# Johnson.net
KiCad netlist of a schematic drawn in EAGLE
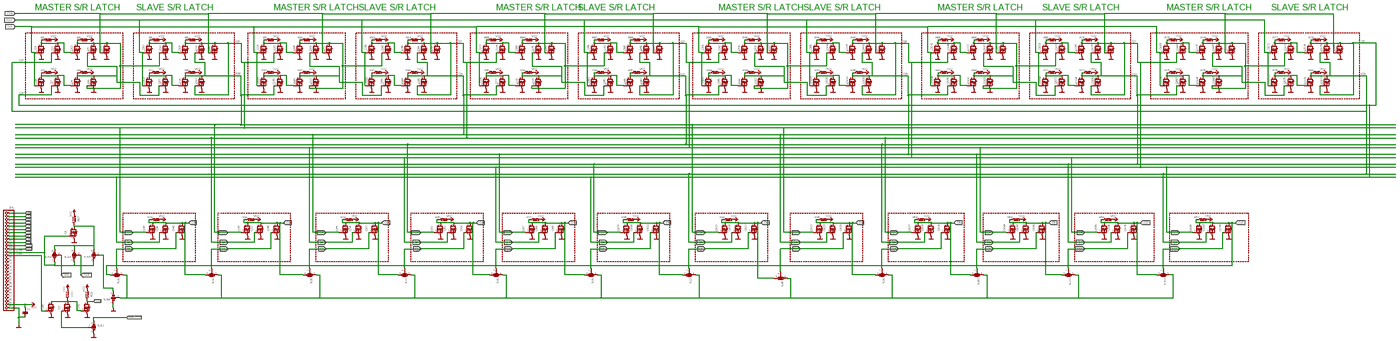
[diagram p0: schematic, sheet 1, overview]
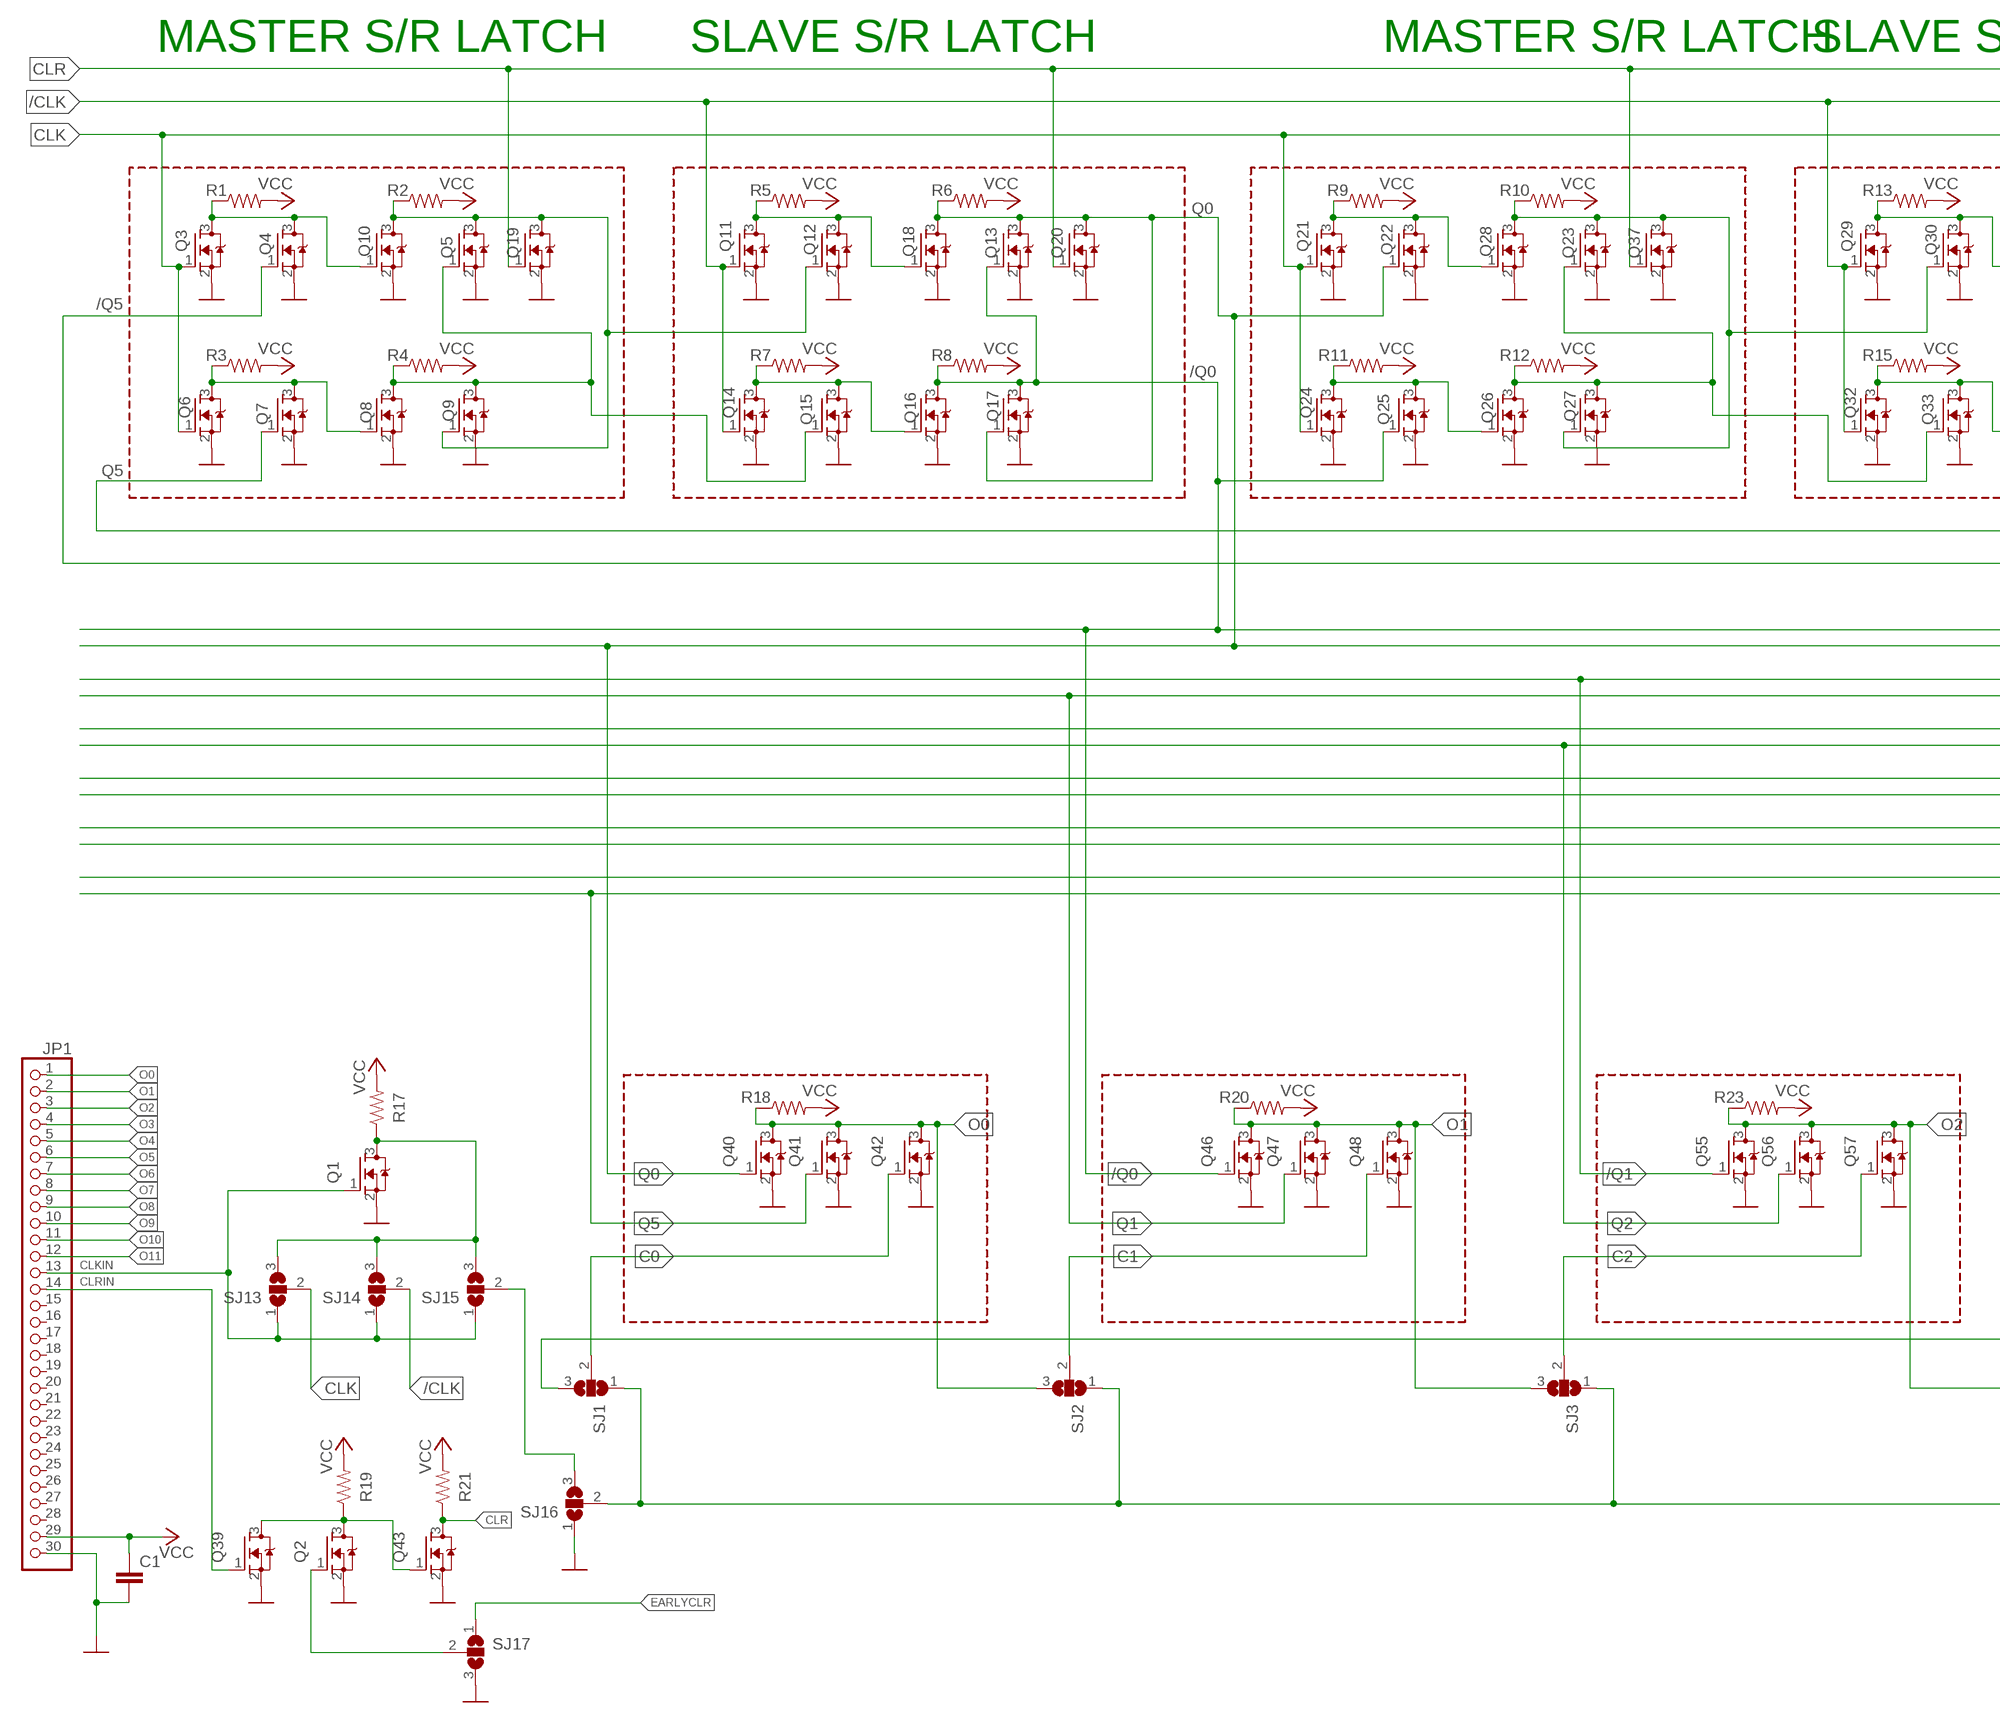
[diagram p1: schematic, sheet 1, part 1 of 4]
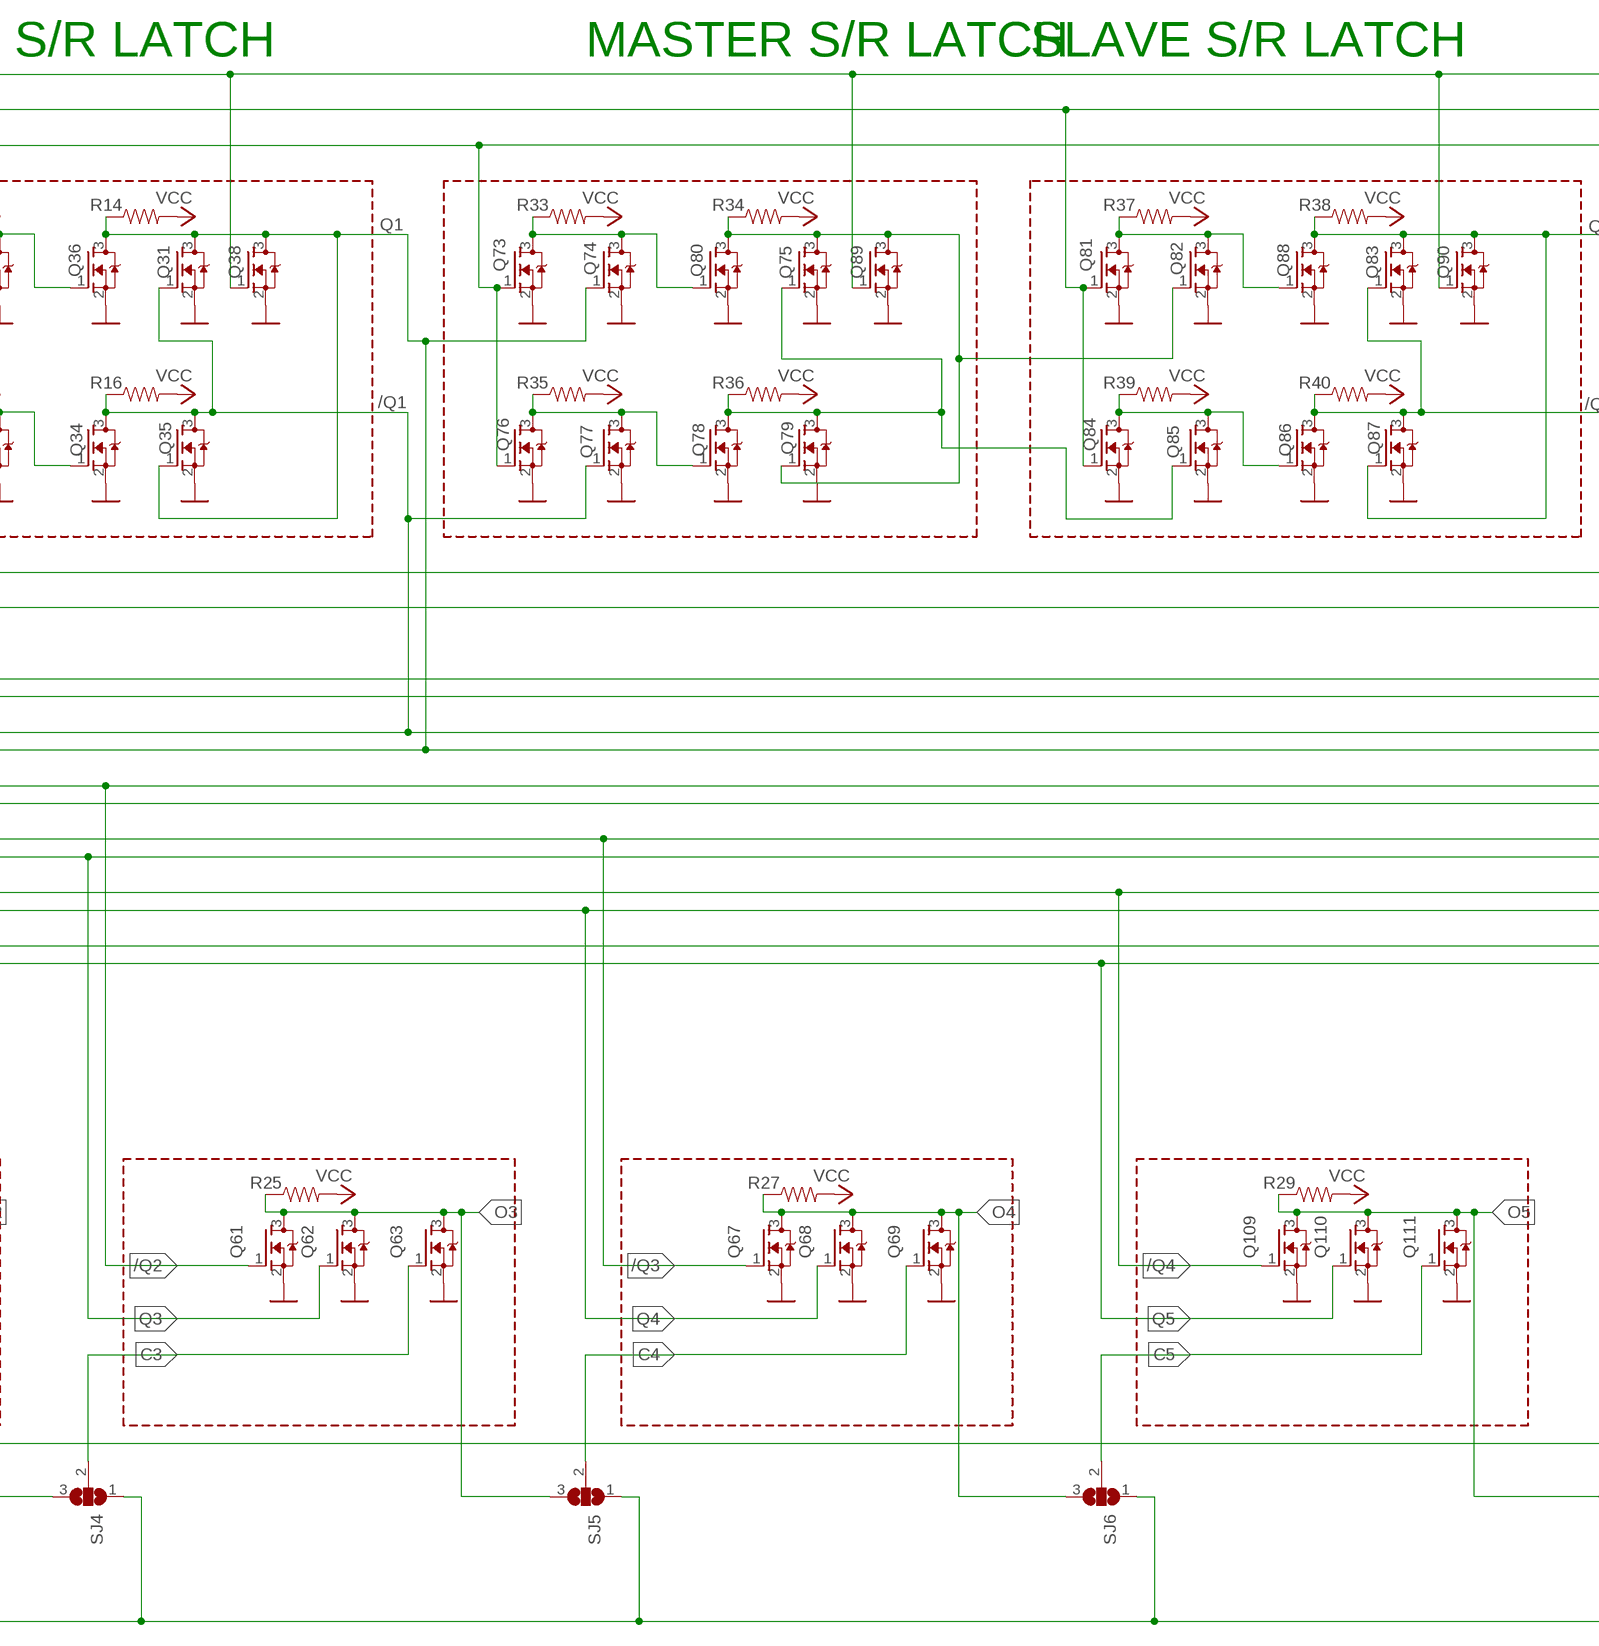
[diagram p2: schematic, sheet 1, part 2 of 4]
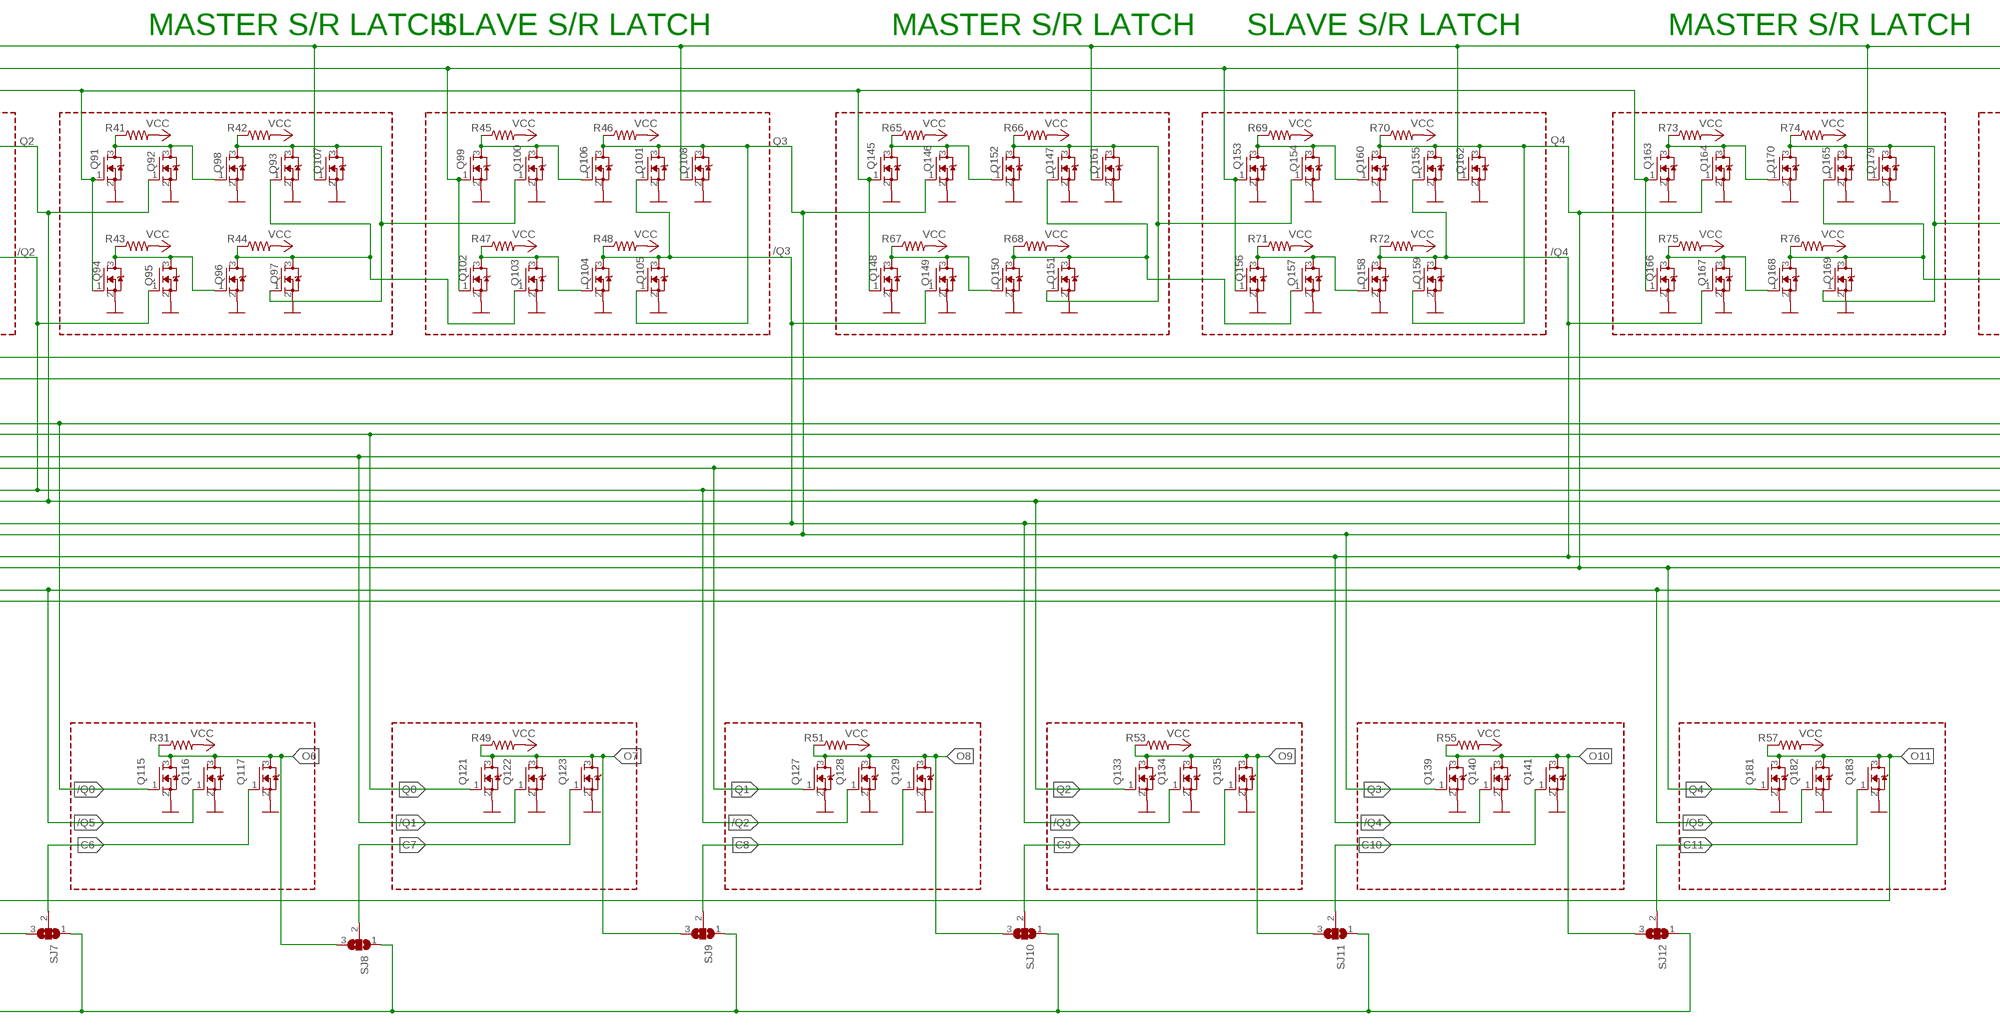
[diagram p3: schematic, sheet 1, part 3 of 4]
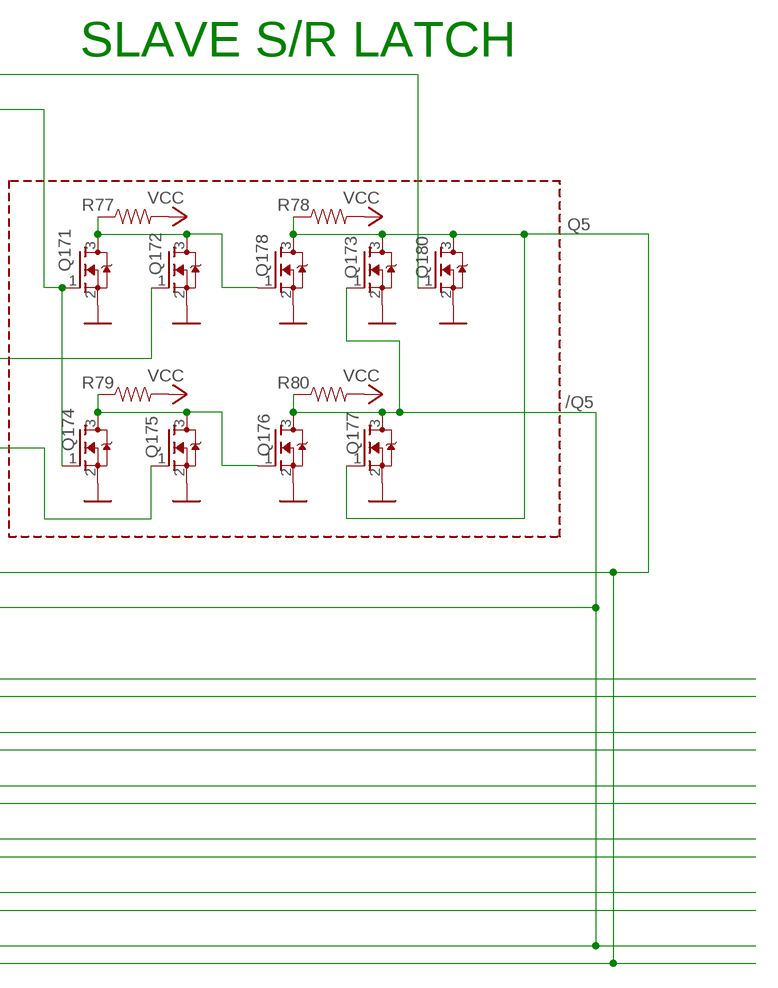
[diagram p4: schematic, sheet 1, part 4 of 4]

(export (version "E")
  (design (tool "Eeschema 10.0.6"))
  (components
    (comp (ref "C1")
      (value "C-EUC0805")
      (footprint "eagle-import:C0805")
      (libsource (lib "eagle-import") (part "C-EUC0805"))
    )
    (comp (ref "JP1")
      (value "PINHD-1X30")
      (footprint "eagle-import:1X30")
      (libsource (lib "eagle-import") (part "PINHD-1X30"))
    )
    (comp (ref "Q1")
      (value "310mA/60V/1.6Ω")
      (footprint "eagle-import:SOT23")
      (libsource (lib "eagle-import") (part "NMOSREFLOW"))
    )
    (comp (ref "Q2")
      (value "310mA/60V/1.6Ω")
      (footprint "eagle-import:SOT23")
      (libsource (lib "eagle-import") (part "NMOSREFLOW"))
    )
    (comp (ref "Q3")
      (value "310mA/60V/1.6Ω")
      (footprint "eagle-import:SOT23")
      (fields (field (name "SPICEPREFIX") "M"))
      (libsource (lib "eagle-import") (part "NMOSREFLOW"))
    )
    (comp (ref "Q4")
      (value "310mA/60V/1.6Ω")
      (footprint "eagle-import:SOT23")
      (libsource (lib "eagle-import") (part "NMOSREFLOW"))
    )
    (comp (ref "Q5")
      (value "310mA/60V/1.6Ω")
      (footprint "eagle-import:SOT23")
      (libsource (lib "eagle-import") (part "NMOSREFLOW"))
    )
    (comp (ref "Q6")
      (value "310mA/60V/1.6Ω")
      (footprint "eagle-import:SOT23")
      (libsource (lib "eagle-import") (part "NMOSREFLOW"))
    )
    (comp (ref "Q7")
      (value "310mA/60V/1.6Ω")
      (footprint "eagle-import:SOT23")
      (libsource (lib "eagle-import") (part "NMOSREFLOW"))
    )
    (comp (ref "Q8")
      (value "310mA/60V/1.6Ω")
      (footprint "eagle-import:SOT23")
      (libsource (lib "eagle-import") (part "NMOSREFLOW"))
    )
    (comp (ref "Q9")
      (value "310mA/60V/1.6Ω")
      (footprint "eagle-import:SOT23")
      (libsource (lib "eagle-import") (part "NMOSREFLOW"))
    )
    (comp (ref "Q10")
      (value "310mA/60V/1.6Ω")
      (footprint "eagle-import:SOT23")
      (fields (field (name "SPICEPREFIX") "M"))
      (libsource (lib "eagle-import") (part "NMOSREFLOW"))
    )
    (comp (ref "Q11")
      (value "310mA/60V/1.6Ω")
      (footprint "eagle-import:SOT23")
      (fields (field (name "SPICEPREFIX") "M"))
      (libsource (lib "eagle-import") (part "NMOSREFLOW"))
    )
    (comp (ref "Q12")
      (value "310mA/60V/1.6Ω")
      (footprint "eagle-import:SOT23")
      (libsource (lib "eagle-import") (part "NMOSREFLOW"))
    )
    (comp (ref "Q13")
      (value "310mA/60V/1.6Ω")
      (footprint "eagle-import:SOT23")
      (libsource (lib "eagle-import") (part "NMOSREFLOW"))
    )
    (comp (ref "Q14")
      (value "310mA/60V/1.6Ω")
      (footprint "eagle-import:SOT23")
      (libsource (lib "eagle-import") (part "NMOSREFLOW"))
    )
    (comp (ref "Q15")
      (value "310mA/60V/1.6Ω")
      (footprint "eagle-import:SOT23")
      (libsource (lib "eagle-import") (part "NMOSREFLOW"))
    )
    (comp (ref "Q16")
      (value "310mA/60V/1.6Ω")
      (footprint "eagle-import:SOT23")
      (libsource (lib "eagle-import") (part "NMOSREFLOW"))
    )
    (comp (ref "Q17")
      (value "310mA/60V/1.6Ω")
      (footprint "eagle-import:SOT23")
      (libsource (lib "eagle-import") (part "NMOSREFLOW"))
    )
    (comp (ref "Q18")
      (value "310mA/60V/1.6Ω")
      (footprint "eagle-import:SOT23")
      (fields (field (name "SPICEPREFIX") "M"))
      (libsource (lib "eagle-import") (part "NMOSREFLOW"))
    )
    (comp (ref "Q19")
      (value "310mA/60V/1.6Ω")
      (footprint "eagle-import:SOT23")
      (libsource (lib "eagle-import") (part "NMOSREFLOW"))
    )
    (comp (ref "Q20")
      (value "310mA/60V/1.6Ω")
      (footprint "eagle-import:SOT23")
      (libsource (lib "eagle-import") (part "NMOSREFLOW"))
    )
    (comp (ref "Q21")
      (value "310mA/60V/1.6Ω")
      (footprint "eagle-import:SOT23")
      (fields (field (name "SPICEPREFIX") "M"))
      (libsource (lib "eagle-import") (part "NMOSREFLOW"))
    )
    (comp (ref "Q22")
      (value "310mA/60V/1.6Ω")
      (footprint "eagle-import:SOT23")
      (libsource (lib "eagle-import") (part "NMOSREFLOW"))
    )
    (comp (ref "Q23")
      (value "310mA/60V/1.6Ω")
      (footprint "eagle-import:SOT23")
      (libsource (lib "eagle-import") (part "NMOSREFLOW"))
    )
    (comp (ref "Q24")
      (value "310mA/60V/1.6Ω")
      (footprint "eagle-import:SOT23")
      (libsource (lib "eagle-import") (part "NMOSREFLOW"))
    )
    (comp (ref "Q25")
      (value "310mA/60V/1.6Ω")
      (footprint "eagle-import:SOT23")
      (libsource (lib "eagle-import") (part "NMOSREFLOW"))
    )
    (comp (ref "Q26")
      (value "310mA/60V/1.6Ω")
      (footprint "eagle-import:SOT23")
      (libsource (lib "eagle-import") (part "NMOSREFLOW"))
    )
    (comp (ref "Q27")
      (value "310mA/60V/1.6Ω")
      (footprint "eagle-import:SOT23")
      (libsource (lib "eagle-import") (part "NMOSREFLOW"))
    )
    (comp (ref "Q28")
      (value "310mA/60V/1.6Ω")
      (footprint "eagle-import:SOT23")
      (fields (field (name "SPICEPREFIX") "M"))
      (libsource (lib "eagle-import") (part "NMOSREFLOW"))
    )
    (comp (ref "Q29")
      (value "310mA/60V/1.6Ω")
      (footprint "eagle-import:SOT23")
      (fields (field (name "SPICEPREFIX") "M"))
      (libsource (lib "eagle-import") (part "NMOSREFLOW"))
    )
    (comp (ref "Q30")
      (value "310mA/60V/1.6Ω")
      (footprint "eagle-import:SOT23")
      (libsource (lib "eagle-import") (part "NMOSREFLOW"))
    )
    (comp (ref "Q31")
      (value "310mA/60V/1.6Ω")
      (footprint "eagle-import:SOT23")
      (libsource (lib "eagle-import") (part "NMOSREFLOW"))
    )
    (comp (ref "Q32")
      (value "310mA/60V/1.6Ω")
      (footprint "eagle-import:SOT23")
      (libsource (lib "eagle-import") (part "NMOSREFLOW"))
    )
    (comp (ref "Q33")
      (value "310mA/60V/1.6Ω")
      (footprint "eagle-import:SOT23")
      (libsource (lib "eagle-import") (part "NMOSREFLOW"))
    )
    (comp (ref "Q34")
      (value "310mA/60V/1.6Ω")
      (footprint "eagle-import:SOT23")
      (libsource (lib "eagle-import") (part "NMOSREFLOW"))
    )
    (comp (ref "Q35")
      (value "310mA/60V/1.6Ω")
      (footprint "eagle-import:SOT23")
      (libsource (lib "eagle-import") (part "NMOSREFLOW"))
    )
    (comp (ref "Q36")
      (value "310mA/60V/1.6Ω")
      (footprint "eagle-import:SOT23")
      (fields (field (name "SPICEPREFIX") "M"))
      (libsource (lib "eagle-import") (part "NMOSREFLOW"))
    )
    (comp (ref "Q37")
      (value "310mA/60V/1.6Ω")
      (footprint "eagle-import:SOT23")
      (libsource (lib "eagle-import") (part "NMOSREFLOW"))
    )
    (comp (ref "Q38")
      (value "310mA/60V/1.6Ω")
      (footprint "eagle-import:SOT23")
      (libsource (lib "eagle-import") (part "NMOSREFLOW"))
    )
    (comp (ref "Q39")
      (value "310mA/60V/1.6Ω")
      (footprint "eagle-import:SOT23")
      (libsource (lib "eagle-import") (part "NMOSREFLOW"))
    )
    (comp (ref "Q40")
      (value "310mA/60V/1.6Ω")
      (footprint "eagle-import:SOT23")
      (libsource (lib "eagle-import") (part "NMOSREFLOW"))
    )
    (comp (ref "Q41")
      (value "310mA/60V/1.6Ω")
      (footprint "eagle-import:SOT23")
      (libsource (lib "eagle-import") (part "NMOSREFLOW"))
    )
    (comp (ref "Q42")
      (value "310mA/60V/1.6Ω")
      (footprint "eagle-import:SOT23")
      (libsource (lib "eagle-import") (part "NMOSREFLOW"))
    )
    (comp (ref "Q43")
      (value "310mA/60V/1.6Ω")
      (footprint "eagle-import:SOT23")
      (libsource (lib "eagle-import") (part "NMOSREFLOW"))
    )
    (comp (ref "Q46")
      (value "310mA/60V/1.6Ω")
      (footprint "eagle-import:SOT23")
      (libsource (lib "eagle-import") (part "NMOSREFLOW"))
    )
    (comp (ref "Q47")
      (value "310mA/60V/1.6Ω")
      (footprint "eagle-import:SOT23")
      (libsource (lib "eagle-import") (part "NMOSREFLOW"))
    )
    (comp (ref "Q48")
      (value "310mA/60V/1.6Ω")
      (footprint "eagle-import:SOT23")
      (libsource (lib "eagle-import") (part "NMOSREFLOW"))
    )
    (comp (ref "Q55")
      (value "310mA/60V/1.6Ω")
      (footprint "eagle-import:SOT23")
      (libsource (lib "eagle-import") (part "NMOSREFLOW"))
    )
    (comp (ref "Q56")
      (value "310mA/60V/1.6Ω")
      (footprint "eagle-import:SOT23")
      (libsource (lib "eagle-import") (part "NMOSREFLOW"))
    )
    (comp (ref "Q57")
      (value "310mA/60V/1.6Ω")
      (footprint "eagle-import:SOT23")
      (libsource (lib "eagle-import") (part "NMOSREFLOW"))
    )
    (comp (ref "Q61")
      (value "310mA/60V/1.6Ω")
      (footprint "eagle-import:SOT23")
      (libsource (lib "eagle-import") (part "NMOSREFLOW"))
    )
    (comp (ref "Q62")
      (value "310mA/60V/1.6Ω")
      (footprint "eagle-import:SOT23")
      (libsource (lib "eagle-import") (part "NMOSREFLOW"))
    )
    (comp (ref "Q63")
      (value "310mA/60V/1.6Ω")
      (footprint "eagle-import:SOT23")
      (libsource (lib "eagle-import") (part "NMOSREFLOW"))
    )
    (comp (ref "Q67")
      (value "310mA/60V/1.6Ω")
      (footprint "eagle-import:SOT23")
      (libsource (lib "eagle-import") (part "NMOSREFLOW"))
    )
    (comp (ref "Q68")
      (value "310mA/60V/1.6Ω")
      (footprint "eagle-import:SOT23")
      (libsource (lib "eagle-import") (part "NMOSREFLOW"))
    )
    (comp (ref "Q69")
      (value "310mA/60V/1.6Ω")
      (footprint "eagle-import:SOT23")
      (libsource (lib "eagle-import") (part "NMOSREFLOW"))
    )
    (comp (ref "Q73")
      (value "310mA/60V/1.6Ω")
      (footprint "eagle-import:SOT23")
      (fields (field (name "SPICEPREFIX") "M"))
      (libsource (lib "eagle-import") (part "NMOSREFLOW"))
    )
    (comp (ref "Q74")
      (value "310mA/60V/1.6Ω")
      (footprint "eagle-import:SOT23")
      (libsource (lib "eagle-import") (part "NMOSREFLOW"))
    )
    (comp (ref "Q75")
      (value "310mA/60V/1.6Ω")
      (footprint "eagle-import:SOT23")
      (libsource (lib "eagle-import") (part "NMOSREFLOW"))
    )
    (comp (ref "Q76")
      (value "310mA/60V/1.6Ω")
      (footprint "eagle-import:SOT23")
      (libsource (lib "eagle-import") (part "NMOSREFLOW"))
    )
    (comp (ref "Q77")
      (value "310mA/60V/1.6Ω")
      (footprint "eagle-import:SOT23")
      (libsource (lib "eagle-import") (part "NMOSREFLOW"))
    )
    (comp (ref "Q78")
      (value "310mA/60V/1.6Ω")
      (footprint "eagle-import:SOT23")
      (libsource (lib "eagle-import") (part "NMOSREFLOW"))
    )
    (comp (ref "Q79")
      (value "310mA/60V/1.6Ω")
      (footprint "eagle-import:SOT23")
      (libsource (lib "eagle-import") (part "NMOSREFLOW"))
    )
    (comp (ref "Q80")
      (value "310mA/60V/1.6Ω")
      (footprint "eagle-import:SOT23")
      (fields (field (name "SPICEPREFIX") "M"))
      (libsource (lib "eagle-import") (part "NMOSREFLOW"))
    )
    (comp (ref "Q81")
      (value "310mA/60V/1.6Ω")
      (footprint "eagle-import:SOT23")
      (fields (field (name "SPICEPREFIX") "M"))
      (libsource (lib "eagle-import") (part "NMOSREFLOW"))
    )
    (comp (ref "Q82")
      (value "310mA/60V/1.6Ω")
      (footprint "eagle-import:SOT23")
      (libsource (lib "eagle-import") (part "NMOSREFLOW"))
    )
    (comp (ref "Q83")
      (value "310mA/60V/1.6Ω")
      (footprint "eagle-import:SOT23")
      (libsource (lib "eagle-import") (part "NMOSREFLOW"))
    )
    (comp (ref "Q84")
      (value "310mA/60V/1.6Ω")
      (footprint "eagle-import:SOT23")
      (libsource (lib "eagle-import") (part "NMOSREFLOW"))
    )
    (comp (ref "Q85")
      (value "310mA/60V/1.6Ω")
      (footprint "eagle-import:SOT23")
      (libsource (lib "eagle-import") (part "NMOSREFLOW"))
    )
    (comp (ref "Q86")
      (value "310mA/60V/1.6Ω")
      (footprint "eagle-import:SOT23")
      (libsource (lib "eagle-import") (part "NMOSREFLOW"))
    )
    (comp (ref "Q87")
      (value "310mA/60V/1.6Ω")
      (footprint "eagle-import:SOT23")
      (libsource (lib "eagle-import") (part "NMOSREFLOW"))
    )
    (comp (ref "Q88")
      (value "310mA/60V/1.6Ω")
      (footprint "eagle-import:SOT23")
      (fields (field (name "SPICEPREFIX") "M"))
      (libsource (lib "eagle-import") (part "NMOSREFLOW"))
    )
    (comp (ref "Q89")
      (value "310mA/60V/1.6Ω")
      (footprint "eagle-import:SOT23")
      (libsource (lib "eagle-import") (part "NMOSREFLOW"))
    )
    (comp (ref "Q90")
      (value "310mA/60V/1.6Ω")
      (footprint "eagle-import:SOT23")
      (libsource (lib "eagle-import") (part "NMOSREFLOW"))
    )
    (comp (ref "Q91")
      (value "310mA/60V/1.6Ω")
      (footprint "eagle-import:SOT23")
      (fields (field (name "SPICEPREFIX") "M"))
      (libsource (lib "eagle-import") (part "NMOSREFLOW"))
    )
    (comp (ref "Q92")
      (value "310mA/60V/1.6Ω")
      (footprint "eagle-import:SOT23")
      (libsource (lib "eagle-import") (part "NMOSREFLOW"))
    )
    (comp (ref "Q93")
      (value "310mA/60V/1.6Ω")
      (footprint "eagle-import:SOT23")
      (libsource (lib "eagle-import") (part "NMOSREFLOW"))
    )
    (comp (ref "Q94")
      (value "310mA/60V/1.6Ω")
      (footprint "eagle-import:SOT23")
      (libsource (lib "eagle-import") (part "NMOSREFLOW"))
    )
    (comp (ref "Q95")
      (value "310mA/60V/1.6Ω")
      (footprint "eagle-import:SOT23")
      (libsource (lib "eagle-import") (part "NMOSREFLOW"))
    )
    (comp (ref "Q96")
      (value "310mA/60V/1.6Ω")
      (footprint "eagle-import:SOT23")
      (libsource (lib "eagle-import") (part "NMOSREFLOW"))
    )
    (comp (ref "Q97")
      (value "310mA/60V/1.6Ω")
      (footprint "eagle-import:SOT23")
      (libsource (lib "eagle-import") (part "NMOSREFLOW"))
    )
    (comp (ref "Q98")
      (value "310mA/60V/1.6Ω")
      (footprint "eagle-import:SOT23")
      (fields (field (name "SPICEPREFIX") "M"))
      (libsource (lib "eagle-import") (part "NMOSREFLOW"))
    )
    (comp (ref "Q99")
      (value "310mA/60V/1.6Ω")
      (footprint "eagle-import:SOT23")
      (fields (field (name "SPICEPREFIX") "M"))
      (libsource (lib "eagle-import") (part "NMOSREFLOW"))
    )
    (comp (ref "Q100")
      (value "310mA/60V/1.6Ω")
      (footprint "eagle-import:SOT23")
      (libsource (lib "eagle-import") (part "NMOSREFLOW"))
    )
    (comp (ref "Q101")
      (value "310mA/60V/1.6Ω")
      (footprint "eagle-import:SOT23")
      (libsource (lib "eagle-import") (part "NMOSREFLOW"))
    )
    (comp (ref "Q102")
      (value "310mA/60V/1.6Ω")
      (footprint "eagle-import:SOT23")
      (libsource (lib "eagle-import") (part "NMOSREFLOW"))
    )
    (comp (ref "Q103")
      (value "310mA/60V/1.6Ω")
      (footprint "eagle-import:SOT23")
      (libsource (lib "eagle-import") (part "NMOSREFLOW"))
    )
    (comp (ref "Q104")
      (value "310mA/60V/1.6Ω")
      (footprint "eagle-import:SOT23")
      (libsource (lib "eagle-import") (part "NMOSREFLOW"))
    )
    (comp (ref "Q105")
      (value "310mA/60V/1.6Ω")
      (footprint "eagle-import:SOT23")
      (libsource (lib "eagle-import") (part "NMOSREFLOW"))
    )
    (comp (ref "Q106")
      (value "310mA/60V/1.6Ω")
      (footprint "eagle-import:SOT23")
      (fields (field (name "SPICEPREFIX") "M"))
      (libsource (lib "eagle-import") (part "NMOSREFLOW"))
    )
    (comp (ref "Q107")
      (value "310mA/60V/1.6Ω")
      (footprint "eagle-import:SOT23")
      (libsource (lib "eagle-import") (part "NMOSREFLOW"))
    )
    (comp (ref "Q108")
      (value "310mA/60V/1.6Ω")
      (footprint "eagle-import:SOT23")
      (libsource (lib "eagle-import") (part "NMOSREFLOW"))
    )
    (comp (ref "Q109")
      (value "310mA/60V/1.6Ω")
      (footprint "eagle-import:SOT23")
      (libsource (lib "eagle-import") (part "NMOSREFLOW"))
    )
    (comp (ref "Q110")
      (value "310mA/60V/1.6Ω")
      (footprint "eagle-import:SOT23")
      (libsource (lib "eagle-import") (part "NMOSREFLOW"))
    )
    (comp (ref "Q111")
      (value "310mA/60V/1.6Ω")
      (footprint "eagle-import:SOT23")
      (libsource (lib "eagle-import") (part "NMOSREFLOW"))
    )
    (comp (ref "Q115")
      (value "310mA/60V/1.6Ω")
      (footprint "eagle-import:SOT23")
      (libsource (lib "eagle-import") (part "NMOSREFLOW"))
    )
    (comp (ref "Q116")
      (value "310mA/60V/1.6Ω")
      (footprint "eagle-import:SOT23")
      (libsource (lib "eagle-import") (part "NMOSREFLOW"))
    )
    (comp (ref "Q117")
      (value "310mA/60V/1.6Ω")
      (footprint "eagle-import:SOT23")
      (libsource (lib "eagle-import") (part "NMOSREFLOW"))
    )
    (comp (ref "Q121")
      (value "310mA/60V/1.6Ω")
      (footprint "eagle-import:SOT23")
      (libsource (lib "eagle-import") (part "NMOSREFLOW"))
    )
    (comp (ref "Q122")
      (value "310mA/60V/1.6Ω")
      (footprint "eagle-import:SOT23")
      (libsource (lib "eagle-import") (part "NMOSREFLOW"))
    )
    (comp (ref "Q123")
      (value "310mA/60V/1.6Ω")
      (footprint "eagle-import:SOT23")
      (libsource (lib "eagle-import") (part "NMOSREFLOW"))
    )
    (comp (ref "Q127")
      (value "310mA/60V/1.6Ω")
      (footprint "eagle-import:SOT23")
      (libsource (lib "eagle-import") (part "NMOSREFLOW"))
    )
    (comp (ref "Q128")
      (value "310mA/60V/1.6Ω")
      (footprint "eagle-import:SOT23")
      (libsource (lib "eagle-import") (part "NMOSREFLOW"))
    )
    (comp (ref "Q129")
      (value "310mA/60V/1.6Ω")
      (footprint "eagle-import:SOT23")
      (libsource (lib "eagle-import") (part "NMOSREFLOW"))
    )
    (comp (ref "Q133")
      (value "310mA/60V/1.6Ω")
      (footprint "eagle-import:SOT23")
      (libsource (lib "eagle-import") (part "NMOSREFLOW"))
    )
    (comp (ref "Q134")
      (value "310mA/60V/1.6Ω")
      (footprint "eagle-import:SOT23")
      (libsource (lib "eagle-import") (part "NMOSREFLOW"))
    )
    (comp (ref "Q135")
      (value "310mA/60V/1.6Ω")
      (footprint "eagle-import:SOT23")
      (libsource (lib "eagle-import") (part "NMOSREFLOW"))
    )
    (comp (ref "Q139")
      (value "310mA/60V/1.6Ω")
      (footprint "eagle-import:SOT23")
      (libsource (lib "eagle-import") (part "NMOSREFLOW"))
    )
    (comp (ref "Q140")
      (value "310mA/60V/1.6Ω")
      (footprint "eagle-import:SOT23")
      (libsource (lib "eagle-import") (part "NMOSREFLOW"))
    )
    (comp (ref "Q141")
      (value "310mA/60V/1.6Ω")
      (footprint "eagle-import:SOT23")
      (libsource (lib "eagle-import") (part "NMOSREFLOW"))
    )
    (comp (ref "Q145")
      (value "310mA/60V/1.6Ω")
      (footprint "eagle-import:SOT23")
      (fields (field (name "SPICEPREFIX") "M"))
      (libsource (lib "eagle-import") (part "NMOSREFLOW"))
    )
    (comp (ref "Q146")
      (value "310mA/60V/1.6Ω")
      (footprint "eagle-import:SOT23")
      (libsource (lib "eagle-import") (part "NMOSREFLOW"))
    )
    (comp (ref "Q147")
      (value "310mA/60V/1.6Ω")
      (footprint "eagle-import:SOT23")
      (libsource (lib "eagle-import") (part "NMOSREFLOW"))
    )
    (comp (ref "Q148")
      (value "310mA/60V/1.6Ω")
      (footprint "eagle-import:SOT23")
      (libsource (lib "eagle-import") (part "NMOSREFLOW"))
    )
    (comp (ref "Q149")
      (value "310mA/60V/1.6Ω")
      (footprint "eagle-import:SOT23")
      (libsource (lib "eagle-import") (part "NMOSREFLOW"))
    )
    (comp (ref "Q150")
      (value "310mA/60V/1.6Ω")
      (footprint "eagle-import:SOT23")
      (libsource (lib "eagle-import") (part "NMOSREFLOW"))
    )
    (comp (ref "Q151")
      (value "310mA/60V/1.6Ω")
      (footprint "eagle-import:SOT23")
      (libsource (lib "eagle-import") (part "NMOSREFLOW"))
    )
    (comp (ref "Q152")
      (value "310mA/60V/1.6Ω")
      (footprint "eagle-import:SOT23")
      (fields (field (name "SPICEPREFIX") "M"))
      (libsource (lib "eagle-import") (part "NMOSREFLOW"))
    )
    (comp (ref "Q153")
      (value "310mA/60V/1.6Ω")
      (footprint "eagle-import:SOT23")
      (fields (field (name "SPICEPREFIX") "M"))
      (libsource (lib "eagle-import") (part "NMOSREFLOW"))
    )
    (comp (ref "Q154")
      (value "310mA/60V/1.6Ω")
      (footprint "eagle-import:SOT23")
      (libsource (lib "eagle-import") (part "NMOSREFLOW"))
    )
    (comp (ref "Q155")
      (value "310mA/60V/1.6Ω")
      (footprint "eagle-import:SOT23")
      (libsource (lib "eagle-import") (part "NMOSREFLOW"))
    )
    (comp (ref "Q156")
      (value "310mA/60V/1.6Ω")
      (footprint "eagle-import:SOT23")
      (libsource (lib "eagle-import") (part "NMOSREFLOW"))
    )
    (comp (ref "Q157")
      (value "310mA/60V/1.6Ω")
      (footprint "eagle-import:SOT23")
      (libsource (lib "eagle-import") (part "NMOSREFLOW"))
    )
    (comp (ref "Q158")
      (value "310mA/60V/1.6Ω")
      (footprint "eagle-import:SOT23")
      (libsource (lib "eagle-import") (part "NMOSREFLOW"))
    )
    (comp (ref "Q159")
      (value "310mA/60V/1.6Ω")
      (footprint "eagle-import:SOT23")
      (libsource (lib "eagle-import") (part "NMOSREFLOW"))
    )
    (comp (ref "Q160")
      (value "310mA/60V/1.6Ω")
      (footprint "eagle-import:SOT23")
      (fields (field (name "SPICEPREFIX") "M"))
      (libsource (lib "eagle-import") (part "NMOSREFLOW"))
    )
    (comp (ref "Q161")
      (value "310mA/60V/1.6Ω")
      (footprint "eagle-import:SOT23")
      (libsource (lib "eagle-import") (part "NMOSREFLOW"))
    )
    (comp (ref "Q162")
      (value "310mA/60V/1.6Ω")
      (footprint "eagle-import:SOT23")
      (libsource (lib "eagle-import") (part "NMOSREFLOW"))
    )
    (comp (ref "Q163")
      (value "310mA/60V/1.6Ω")
      (footprint "eagle-import:SOT23")
      (fields (field (name "SPICEPREFIX") "M"))
      (libsource (lib "eagle-import") (part "NMOSREFLOW"))
    )
    (comp (ref "Q164")
      (value "310mA/60V/1.6Ω")
      (footprint "eagle-import:SOT23")
      (libsource (lib "eagle-import") (part "NMOSREFLOW"))
    )
    (comp (ref "Q165")
      (value "310mA/60V/1.6Ω")
      (footprint "eagle-import:SOT23")
      (libsource (lib "eagle-import") (part "NMOSREFLOW"))
    )
    (comp (ref "Q166")
      (value "310mA/60V/1.6Ω")
      (footprint "eagle-import:SOT23")
      (libsource (lib "eagle-import") (part "NMOSREFLOW"))
    )
    (comp (ref "Q167")
      (value "310mA/60V/1.6Ω")
      (footprint "eagle-import:SOT23")
      (libsource (lib "eagle-import") (part "NMOSREFLOW"))
    )
    (comp (ref "Q168")
      (value "310mA/60V/1.6Ω")
      (footprint "eagle-import:SOT23")
      (libsource (lib "eagle-import") (part "NMOSREFLOW"))
    )
    (comp (ref "Q169")
      (value "310mA/60V/1.6Ω")
      (footprint "eagle-import:SOT23")
      (libsource (lib "eagle-import") (part "NMOSREFLOW"))
    )
    (comp (ref "Q170")
      (value "310mA/60V/1.6Ω")
      (footprint "eagle-import:SOT23")
      (fields (field (name "SPICEPREFIX") "M"))
      (libsource (lib "eagle-import") (part "NMOSREFLOW"))
    )
    (comp (ref "Q171")
      (value "310mA/60V/1.6Ω")
      (footprint "eagle-import:SOT23")
      (fields (field (name "SPICEPREFIX") "M"))
      (libsource (lib "eagle-import") (part "NMOSREFLOW"))
    )
    (comp (ref "Q172")
      (value "310mA/60V/1.6Ω")
      (footprint "eagle-import:SOT23")
      (libsource (lib "eagle-import") (part "NMOSREFLOW"))
    )
    (comp (ref "Q173")
      (value "310mA/60V/1.6Ω")
      (footprint "eagle-import:SOT23")
      (libsource (lib "eagle-import") (part "NMOSREFLOW"))
    )
    (comp (ref "Q174")
      (value "310mA/60V/1.6Ω")
      (footprint "eagle-import:SOT23")
      (libsource (lib "eagle-import") (part "NMOSREFLOW"))
    )
    (comp (ref "Q175")
      (value "310mA/60V/1.6Ω")
      (footprint "eagle-import:SOT23")
      (libsource (lib "eagle-import") (part "NMOSREFLOW"))
    )
    (comp (ref "Q176")
      (value "310mA/60V/1.6Ω")
      (footprint "eagle-import:SOT23")
      (libsource (lib "eagle-import") (part "NMOSREFLOW"))
    )
    (comp (ref "Q177")
      (value "310mA/60V/1.6Ω")
      (footprint "eagle-import:SOT23")
      (libsource (lib "eagle-import") (part "NMOSREFLOW"))
    )
    (comp (ref "Q178")
      (value "310mA/60V/1.6Ω")
      (footprint "eagle-import:SOT23")
      (fields (field (name "SPICEPREFIX") "M"))
      (libsource (lib "eagle-import") (part "NMOSREFLOW"))
    )
    (comp (ref "Q179")
      (value "310mA/60V/1.6Ω")
      (footprint "eagle-import:SOT23")
      (libsource (lib "eagle-import") (part "NMOSREFLOW"))
    )
    (comp (ref "Q180")
      (value "310mA/60V/1.6Ω")
      (footprint "eagle-import:SOT23")
      (libsource (lib "eagle-import") (part "NMOSREFLOW"))
    )
    (comp (ref "Q181")
      (value "310mA/60V/1.6Ω")
      (footprint "eagle-import:SOT23")
      (libsource (lib "eagle-import") (part "NMOSREFLOW"))
    )
    (comp (ref "Q182")
      (value "310mA/60V/1.6Ω")
      (footprint "eagle-import:SOT23")
      (libsource (lib "eagle-import") (part "NMOSREFLOW"))
    )
    (comp (ref "Q183")
      (value "310mA/60V/1.6Ω")
      (footprint "eagle-import:SOT23")
      (libsource (lib "eagle-import") (part "NMOSREFLOW"))
    )
    (comp (ref "R1")
      (value "RESISTOR0805")
      (footprint "eagle-import:0805")
      (libsource (lib "eagle-import") (part "RESISTOR0805"))
    )
    (comp (ref "R2")
      (value "RESISTOR0805")
      (footprint "eagle-import:0805")
      (libsource (lib "eagle-import") (part "RESISTOR0805"))
    )
    (comp (ref "R3")
      (value "RESISTOR0805")
      (footprint "eagle-import:0805")
      (libsource (lib "eagle-import") (part "RESISTOR0805"))
    )
    (comp (ref "R4")
      (value "RESISTOR0805")
      (footprint "eagle-import:0805")
      (libsource (lib "eagle-import") (part "RESISTOR0805"))
    )
    (comp (ref "R5")
      (value "RESISTOR0805")
      (footprint "eagle-import:0805")
      (libsource (lib "eagle-import") (part "RESISTOR0805"))
    )
    (comp (ref "R6")
      (value "RESISTOR0805")
      (footprint "eagle-import:0805")
      (libsource (lib "eagle-import") (part "RESISTOR0805"))
    )
    (comp (ref "R7")
      (value "RESISTOR0805")
      (footprint "eagle-import:0805")
      (libsource (lib "eagle-import") (part "RESISTOR0805"))
    )
    (comp (ref "R8")
      (value "RESISTOR0805")
      (footprint "eagle-import:0805")
      (libsource (lib "eagle-import") (part "RESISTOR0805"))
    )
    (comp (ref "R9")
      (value "RESISTOR0805")
      (footprint "eagle-import:0805")
      (libsource (lib "eagle-import") (part "RESISTOR0805"))
    )
    (comp (ref "R10")
      (value "RESISTOR0805")
      (footprint "eagle-import:0805")
      (libsource (lib "eagle-import") (part "RESISTOR0805"))
    )
    (comp (ref "R11")
      (value "RESISTOR0805")
      (footprint "eagle-import:0805")
      (libsource (lib "eagle-import") (part "RESISTOR0805"))
    )
    (comp (ref "R12")
      (value "RESISTOR0805")
      (footprint "eagle-import:0805")
      (libsource (lib "eagle-import") (part "RESISTOR0805"))
    )
    (comp (ref "R13")
      (value "RESISTOR0805")
      (footprint "eagle-import:0805")
      (libsource (lib "eagle-import") (part "RESISTOR0805"))
    )
    (comp (ref "R14")
      (value "RESISTOR0805")
      (footprint "eagle-import:0805")
      (libsource (lib "eagle-import") (part "RESISTOR0805"))
    )
    (comp (ref "R15")
      (value "RESISTOR0805")
      (footprint "eagle-import:0805")
      (libsource (lib "eagle-import") (part "RESISTOR0805"))
    )
    (comp (ref "R16")
      (value "RESISTOR0805")
      (footprint "eagle-import:0805")
      (libsource (lib "eagle-import") (part "RESISTOR0805"))
    )
    (comp (ref "R17")
      (value "RESISTOR0805")
      (footprint "eagle-import:0805")
      (libsource (lib "eagle-import") (part "RESISTOR0805"))
    )
    (comp (ref "R18")
      (value "RESISTOR0805")
      (footprint "eagle-import:0805")
      (libsource (lib "eagle-import") (part "RESISTOR0805"))
    )
    (comp (ref "R19")
      (value "RESISTOR0805")
      (footprint "eagle-import:0805")
      (libsource (lib "eagle-import") (part "RESISTOR0805"))
    )
    (comp (ref "R20")
      (value "RESISTOR0805")
      (footprint "eagle-import:0805")
      (libsource (lib "eagle-import") (part "RESISTOR0805"))
    )
    (comp (ref "R21")
      (value "RESISTOR0805")
      (footprint "eagle-import:0805")
      (libsource (lib "eagle-import") (part "RESISTOR0805"))
    )
    (comp (ref "R23")
      (value "RESISTOR0805")
      (footprint "eagle-import:0805")
      (libsource (lib "eagle-import") (part "RESISTOR0805"))
    )
    (comp (ref "R25")
      (value "RESISTOR0805")
      (footprint "eagle-import:0805")
      (libsource (lib "eagle-import") (part "RESISTOR0805"))
    )
    (comp (ref "R27")
      (value "RESISTOR0805")
      (footprint "eagle-import:0805")
      (libsource (lib "eagle-import") (part "RESISTOR0805"))
    )
    (comp (ref "R29")
      (value "RESISTOR0805")
      (footprint "eagle-import:0805")
      (libsource (lib "eagle-import") (part "RESISTOR0805"))
    )
    (comp (ref "R31")
      (value "RESISTOR0805")
      (footprint "eagle-import:0805")
      (libsource (lib "eagle-import") (part "RESISTOR0805"))
    )
    (comp (ref "R33")
      (value "RESISTOR0805")
      (footprint "eagle-import:0805")
      (libsource (lib "eagle-import") (part "RESISTOR0805"))
    )
    (comp (ref "R34")
      (value "RESISTOR0805")
      (footprint "eagle-import:0805")
      (libsource (lib "eagle-import") (part "RESISTOR0805"))
    )
    (comp (ref "R35")
      (value "RESISTOR0805")
      (footprint "eagle-import:0805")
      (libsource (lib "eagle-import") (part "RESISTOR0805"))
    )
    (comp (ref "R36")
      (value "RESISTOR0805")
      (footprint "eagle-import:0805")
      (libsource (lib "eagle-import") (part "RESISTOR0805"))
    )
    (comp (ref "R37")
      (value "RESISTOR0805")
      (footprint "eagle-import:0805")
      (libsource (lib "eagle-import") (part "RESISTOR0805"))
    )
    (comp (ref "R38")
      (value "RESISTOR0805")
      (footprint "eagle-import:0805")
      (libsource (lib "eagle-import") (part "RESISTOR0805"))
    )
    (comp (ref "R39")
      (value "RESISTOR0805")
      (footprint "eagle-import:0805")
      (libsource (lib "eagle-import") (part "RESISTOR0805"))
    )
    (comp (ref "R40")
      (value "RESISTOR0805")
      (footprint "eagle-import:0805")
      (libsource (lib "eagle-import") (part "RESISTOR0805"))
    )
    (comp (ref "R41")
      (value "RESISTOR0805")
      (footprint "eagle-import:0805")
      (libsource (lib "eagle-import") (part "RESISTOR0805"))
    )
    (comp (ref "R42")
      (value "RESISTOR0805")
      (footprint "eagle-import:0805")
      (libsource (lib "eagle-import") (part "RESISTOR0805"))
    )
    (comp (ref "R43")
      (value "RESISTOR0805")
      (footprint "eagle-import:0805")
      (libsource (lib "eagle-import") (part "RESISTOR0805"))
    )
    (comp (ref "R44")
      (value "RESISTOR0805")
      (footprint "eagle-import:0805")
      (libsource (lib "eagle-import") (part "RESISTOR0805"))
    )
    (comp (ref "R45")
      (value "RESISTOR0805")
      (footprint "eagle-import:0805")
      (libsource (lib "eagle-import") (part "RESISTOR0805"))
    )
    (comp (ref "R46")
      (value "RESISTOR0805")
      (footprint "eagle-import:0805")
      (libsource (lib "eagle-import") (part "RESISTOR0805"))
    )
    (comp (ref "R47")
      (value "RESISTOR0805")
      (footprint "eagle-import:0805")
      (libsource (lib "eagle-import") (part "RESISTOR0805"))
    )
    (comp (ref "R48")
      (value "RESISTOR0805")
      (footprint "eagle-import:0805")
      (libsource (lib "eagle-import") (part "RESISTOR0805"))
    )
    (comp (ref "R49")
      (value "RESISTOR0805")
      (footprint "eagle-import:0805")
      (libsource (lib "eagle-import") (part "RESISTOR0805"))
    )
    (comp (ref "R51")
      (value "RESISTOR0805")
      (footprint "eagle-import:0805")
      (libsource (lib "eagle-import") (part "RESISTOR0805"))
    )
    (comp (ref "R53")
      (value "RESISTOR0805")
      (footprint "eagle-import:0805")
      (libsource (lib "eagle-import") (part "RESISTOR0805"))
    )
    (comp (ref "R55")
      (value "RESISTOR0805")
      (footprint "eagle-import:0805")
      (libsource (lib "eagle-import") (part "RESISTOR0805"))
    )
    (comp (ref "R57")
      (value "RESISTOR0805")
      (footprint "eagle-import:0805")
      (libsource (lib "eagle-import") (part "RESISTOR0805"))
    )
    (comp (ref "R65")
      (value "RESISTOR0805")
      (footprint "eagle-import:0805")
      (libsource (lib "eagle-import") (part "RESISTOR0805"))
    )
    (comp (ref "R66")
      (value "RESISTOR0805")
      (footprint "eagle-import:0805")
      (libsource (lib "eagle-import") (part "RESISTOR0805"))
    )
    (comp (ref "R67")
      (value "RESISTOR0805")
      (footprint "eagle-import:0805")
      (libsource (lib "eagle-import") (part "RESISTOR0805"))
    )
    (comp (ref "R68")
      (value "RESISTOR0805")
      (footprint "eagle-import:0805")
      (libsource (lib "eagle-import") (part "RESISTOR0805"))
    )
    (comp (ref "R69")
      (value "RESISTOR0805")
      (footprint "eagle-import:0805")
      (libsource (lib "eagle-import") (part "RESISTOR0805"))
    )
    (comp (ref "R70")
      (value "RESISTOR0805")
      (footprint "eagle-import:0805")
      (libsource (lib "eagle-import") (part "RESISTOR0805"))
    )
    (comp (ref "R71")
      (value "RESISTOR0805")
      (footprint "eagle-import:0805")
      (libsource (lib "eagle-import") (part "RESISTOR0805"))
    )
    (comp (ref "R72")
      (value "RESISTOR0805")
      (footprint "eagle-import:0805")
      (libsource (lib "eagle-import") (part "RESISTOR0805"))
    )
    (comp (ref "R73")
      (value "RESISTOR0805")
      (footprint "eagle-import:0805")
      (libsource (lib "eagle-import") (part "RESISTOR0805"))
    )
    (comp (ref "R74")
      (value "RESISTOR0805")
      (footprint "eagle-import:0805")
      (libsource (lib "eagle-import") (part "RESISTOR0805"))
    )
    (comp (ref "R75")
      (value "RESISTOR0805")
      (footprint "eagle-import:0805")
      (libsource (lib "eagle-import") (part "RESISTOR0805"))
    )
    (comp (ref "R76")
      (value "RESISTOR0805")
      (footprint "eagle-import:0805")
      (libsource (lib "eagle-import") (part "RESISTOR0805"))
    )
    (comp (ref "R77")
      (value "RESISTOR0805")
      (footprint "eagle-import:0805")
      (libsource (lib "eagle-import") (part "RESISTOR0805"))
    )
    (comp (ref "R78")
      (value "RESISTOR0805")
      (footprint "eagle-import:0805")
      (libsource (lib "eagle-import") (part "RESISTOR0805"))
    )
    (comp (ref "R79")
      (value "RESISTOR0805")
      (footprint "eagle-import:0805")
      (libsource (lib "eagle-import") (part "RESISTOR0805"))
    )
    (comp (ref "R80")
      (value "RESISTOR0805")
      (footprint "eagle-import:0805")
      (libsource (lib "eagle-import") (part "RESISTOR0805"))
    )
    (comp (ref "SJ1")
      (value "SJ2W")
      (footprint "eagle-import:SJ_2")
      (libsource (lib "eagle-import") (part "SJ2W"))
    )
    (comp (ref "SJ2")
      (value "SJ2W")
      (footprint "eagle-import:SJ_2")
      (libsource (lib "eagle-import") (part "SJ2W"))
    )
    (comp (ref "SJ3")
      (value "SJ2W")
      (footprint "eagle-import:SJ_2")
      (libsource (lib "eagle-import") (part "SJ2W"))
    )
    (comp (ref "SJ4")
      (value "SJ2W")
      (footprint "eagle-import:SJ_2")
      (libsource (lib "eagle-import") (part "SJ2W"))
    )
    (comp (ref "SJ5")
      (value "SJ2W")
      (footprint "eagle-import:SJ_2")
      (libsource (lib "eagle-import") (part "SJ2W"))
    )
    (comp (ref "SJ6")
      (value "SJ2W")
      (footprint "eagle-import:SJ_2")
      (libsource (lib "eagle-import") (part "SJ2W"))
    )
    (comp (ref "SJ7")
      (value "SJ2W")
      (footprint "eagle-import:SJ_2")
      (libsource (lib "eagle-import") (part "SJ2W"))
    )
    (comp (ref "SJ8")
      (value "SJ2W")
      (footprint "eagle-import:SJ_2")
      (libsource (lib "eagle-import") (part "SJ2W"))
    )
    (comp (ref "SJ9")
      (value "SJ2W")
      (footprint "eagle-import:SJ_2")
      (libsource (lib "eagle-import") (part "SJ2W"))
    )
    (comp (ref "SJ10")
      (value "SJ2W")
      (footprint "eagle-import:SJ_2")
      (libsource (lib "eagle-import") (part "SJ2W"))
    )
    (comp (ref "SJ11")
      (value "SJ2W")
      (footprint "eagle-import:SJ_2")
      (libsource (lib "eagle-import") (part "SJ2W"))
    )
    (comp (ref "SJ12")
      (value "SJ2W")
      (footprint "eagle-import:SJ_2")
      (libsource (lib "eagle-import") (part "SJ2W"))
    )
    (comp (ref "SJ13")
      (value "SJ2W")
      (footprint "eagle-import:SJ_2")
      (libsource (lib "eagle-import") (part "SJ2W"))
    )
    (comp (ref "SJ14")
      (value "SJ2W")
      (footprint "eagle-import:SJ_2")
      (libsource (lib "eagle-import") (part "SJ2W"))
    )
    (comp (ref "SJ15")
      (value "SJ2W")
      (footprint "eagle-import:SJ_2")
      (libsource (lib "eagle-import") (part "SJ2W"))
    )
    (comp (ref "SJ16")
      (value "SJ2W")
      (footprint "eagle-import:SJ_2")
      (libsource (lib "eagle-import") (part "SJ2W"))
    )
    (comp (ref "SJ17")
      (value "SJ2W")
      (footprint "eagle-import:SJ_2")
      (libsource (lib "eagle-import") (part "SJ2W"))
    )
  )
  (nets
    (net (code "1") (name "/CLKIN") (class "Default")
      (node (ref "JP1") (pin "13") (pinfunction "13_13") (pintype "passive"))
      (node (ref "Q1") (pin "1") (pinfunction "G_1") (pintype "bidirectional"))
      (node (ref "SJ13") (pin "1") (pinfunction "1_1") (pintype "passive"))
      (node (ref "SJ14") (pin "1") (pinfunction "1_1") (pintype "passive"))
      (node (ref "SJ15") (pin "1") (pinfunction "1_1") (pintype "passive"))
    )
    (net (code "2") (name "/CLRIN") (class "Default")
      (node (ref "JP1") (pin "14") (pinfunction "14_14") (pintype "passive"))
      (node (ref "Q39") (pin "1") (pinfunction "G_1") (pintype "bidirectional"))
    )
    (net (code "3") (name "C0") (class "Default")
      (node (ref "Q42") (pin "1") (pinfunction "G_1") (pintype "bidirectional"))
      (node (ref "SJ1") (pin "2") (pinfunction "2_2") (pintype "passive"))
    )
    (net (code "4") (name "C1") (class "Default")
      (node (ref "Q48") (pin "1") (pinfunction "G_1") (pintype "bidirectional"))
      (node (ref "SJ2") (pin "2") (pinfunction "2_2") (pintype "passive"))
    )
    (net (code "5") (name "C2") (class "Default")
      (node (ref "Q57") (pin "1") (pinfunction "G_1") (pintype "bidirectional"))
      (node (ref "SJ3") (pin "2") (pinfunction "2_2") (pintype "passive"))
    )
    (net (code "6") (name "C3") (class "Default")
      (node (ref "Q63") (pin "1") (pinfunction "G_1") (pintype "bidirectional"))
      (node (ref "SJ4") (pin "2") (pinfunction "2_2") (pintype "passive"))
    )
    (net (code "7") (name "C4") (class "Default")
      (node (ref "Q69") (pin "1") (pinfunction "G_1") (pintype "bidirectional"))
      (node (ref "SJ5") (pin "2") (pinfunction "2_2") (pintype "passive"))
    )
    (net (code "8") (name "C5") (class "Default")
      (node (ref "Q111") (pin "1") (pinfunction "G_1") (pintype "bidirectional"))
      (node (ref "SJ6") (pin "2") (pinfunction "2_2") (pintype "passive"))
    )
    (net (code "9") (name "C6") (class "Default")
      (node (ref "Q117") (pin "1") (pinfunction "G_1") (pintype "bidirectional"))
      (node (ref "SJ7") (pin "2") (pinfunction "2_2") (pintype "passive"))
    )
    (net (code "10") (name "C7") (class "Default")
      (node (ref "Q123") (pin "1") (pinfunction "G_1") (pintype "bidirectional"))
      (node (ref "SJ8") (pin "2") (pinfunction "2_2") (pintype "passive"))
    )
    (net (code "11") (name "C8") (class "Default")
      (node (ref "Q129") (pin "1") (pinfunction "G_1") (pintype "bidirectional"))
      (node (ref "SJ9") (pin "2") (pinfunction "2_2") (pintype "passive"))
    )
    (net (code "12") (name "C9") (class "Default")
      (node (ref "Q135") (pin "1") (pinfunction "G_1") (pintype "bidirectional"))
      (node (ref "SJ10") (pin "2") (pinfunction "2_2") (pintype "passive"))
    )
    (net (code "13") (name "C10") (class "Default")
      (node (ref "Q141") (pin "1") (pinfunction "G_1") (pintype "bidirectional"))
      (node (ref "SJ11") (pin "2") (pinfunction "2_2") (pintype "passive"))
    )
    (net (code "14") (name "C11") (class "Default")
      (node (ref "Q183") (pin "1") (pinfunction "G_1") (pintype "bidirectional"))
      (node (ref "SJ12") (pin "2") (pinfunction "2_2") (pintype "passive"))
    )
    (net (code "15") (name "CLK") (class "Default")
      (node (ref "Q145") (pin "1") (pinfunction "G_1") (pintype "bidirectional"))
      (node (ref "Q148") (pin "1") (pinfunction "G_1") (pintype "bidirectional"))
      (node (ref "Q163") (pin "1") (pinfunction "G_1") (pintype "bidirectional"))
      (node (ref "Q166") (pin "1") (pinfunction "G_1") (pintype "bidirectional"))
      (node (ref "Q21") (pin "1") (pinfunction "G_1") (pintype "bidirectional"))
      (node (ref "Q24") (pin "1") (pinfunction "G_1") (pintype "bidirectional"))
      (node (ref "Q3") (pin "1") (pinfunction "G_1") (pintype "bidirectional"))
      (node (ref "Q6") (pin "1") (pinfunction "G_1") (pintype "bidirectional"))
      (node (ref "Q73") (pin "1") (pinfunction "G_1") (pintype "bidirectional"))
      (node (ref "Q76") (pin "1") (pinfunction "G_1") (pintype "bidirectional"))
      (node (ref "Q91") (pin "1") (pinfunction "G_1") (pintype "bidirectional"))
      (node (ref "Q94") (pin "1") (pinfunction "G_1") (pintype "bidirectional"))
      (node (ref "SJ13") (pin "2") (pinfunction "2_2") (pintype "passive"))
    )
    (net (code "16") (name "CLR") (class "Default")
      (node (ref "Q107") (pin "1") (pinfunction "G_1") (pintype "bidirectional"))
      (node (ref "Q108") (pin "1") (pinfunction "G_1") (pintype "bidirectional"))
      (node (ref "Q161") (pin "1") (pinfunction "G_1") (pintype "bidirectional"))
      (node (ref "Q162") (pin "1") (pinfunction "G_1") (pintype "bidirectional"))
      (node (ref "Q179") (pin "1") (pinfunction "G_1") (pintype "bidirectional"))
      (node (ref "Q180") (pin "1") (pinfunction "G_1") (pintype "bidirectional"))
      (node (ref "Q19") (pin "1") (pinfunction "G_1") (pintype "bidirectional"))
      (node (ref "Q20") (pin "1") (pinfunction "G_1") (pintype "bidirectional"))
      (node (ref "Q37") (pin "1") (pinfunction "G_1") (pintype "bidirectional"))
      (node (ref "Q38") (pin "1") (pinfunction "G_1") (pintype "bidirectional"))
      (node (ref "Q43") (pin "3") (pinfunction "D_3") (pintype "bidirectional"))
      (node (ref "Q89") (pin "1") (pinfunction "G_1") (pintype "bidirectional"))
      (node (ref "Q90") (pin "1") (pinfunction "G_1") (pintype "bidirectional"))
      (node (ref "R21") (pin "1") (pinfunction "1_1") (pintype "passive"))
    )
    (net (code "17") (name "EARLYCLR") (class "Default")
      (node (ref "SJ17") (pin "1") (pinfunction "1_1") (pintype "passive"))
    )
    (net (code "18") (name "GND") (class "Default")
      (node (ref "C1") (pin "2") (pinfunction "2_2") (pintype "passive"))
      (node (ref "JP1") (pin "30") (pinfunction "30_30") (pintype "passive"))
      (node (ref "Q1") (pin "2") (pinfunction "S_2") (pintype "bidirectional"))
      (node (ref "Q10") (pin "2") (pinfunction "S_2") (pintype "bidirectional"))
      (node (ref "Q100") (pin "2") (pinfunction "S_2") (pintype "bidirectional"))
      (node (ref "Q101") (pin "2") (pinfunction "S_2") (pintype "bidirectional"))
      (node (ref "Q102") (pin "2") (pinfunction "S_2") (pintype "bidirectional"))
      (node (ref "Q103") (pin "2") (pinfunction "S_2") (pintype "bidirectional"))
      (node (ref "Q104") (pin "2") (pinfunction "S_2") (pintype "bidirectional"))
      (node (ref "Q105") (pin "2") (pinfunction "S_2") (pintype "bidirectional"))
      (node (ref "Q106") (pin "2") (pinfunction "S_2") (pintype "bidirectional"))
      (node (ref "Q107") (pin "2") (pinfunction "S_2") (pintype "bidirectional"))
      (node (ref "Q108") (pin "2") (pinfunction "S_2") (pintype "bidirectional"))
      (node (ref "Q109") (pin "2") (pinfunction "S_2") (pintype "bidirectional"))
      (node (ref "Q11") (pin "2") (pinfunction "S_2") (pintype "bidirectional"))
      (node (ref "Q110") (pin "2") (pinfunction "S_2") (pintype "bidirectional"))
      (node (ref "Q111") (pin "2") (pinfunction "S_2") (pintype "bidirectional"))
      (node (ref "Q115") (pin "2") (pinfunction "S_2") (pintype "bidirectional"))
      (node (ref "Q116") (pin "2") (pinfunction "S_2") (pintype "bidirectional"))
      (node (ref "Q117") (pin "2") (pinfunction "S_2") (pintype "bidirectional"))
      (node (ref "Q12") (pin "2") (pinfunction "S_2") (pintype "bidirectional"))
      (node (ref "Q121") (pin "2") (pinfunction "S_2") (pintype "bidirectional"))
      (node (ref "Q122") (pin "2") (pinfunction "S_2") (pintype "bidirectional"))
      (node (ref "Q123") (pin "2") (pinfunction "S_2") (pintype "bidirectional"))
      (node (ref "Q127") (pin "2") (pinfunction "S_2") (pintype "bidirectional"))
      (node (ref "Q128") (pin "2") (pinfunction "S_2") (pintype "bidirectional"))
      (node (ref "Q129") (pin "2") (pinfunction "S_2") (pintype "bidirectional"))
      (node (ref "Q13") (pin "2") (pinfunction "S_2") (pintype "bidirectional"))
      (node (ref "Q133") (pin "2") (pinfunction "S_2") (pintype "bidirectional"))
      (node (ref "Q134") (pin "2") (pinfunction "S_2") (pintype "bidirectional"))
      (node (ref "Q135") (pin "2") (pinfunction "S_2") (pintype "bidirectional"))
      (node (ref "Q139") (pin "2") (pinfunction "S_2") (pintype "bidirectional"))
      (node (ref "Q14") (pin "2") (pinfunction "S_2") (pintype "bidirectional"))
      (node (ref "Q140") (pin "2") (pinfunction "S_2") (pintype "bidirectional"))
      (node (ref "Q141") (pin "2") (pinfunction "S_2") (pintype "bidirectional"))
      (node (ref "Q145") (pin "2") (pinfunction "S_2") (pintype "bidirectional"))
      (node (ref "Q146") (pin "2") (pinfunction "S_2") (pintype "bidirectional"))
      (node (ref "Q147") (pin "2") (pinfunction "S_2") (pintype "bidirectional"))
      (node (ref "Q148") (pin "2") (pinfunction "S_2") (pintype "bidirectional"))
      (node (ref "Q149") (pin "2") (pinfunction "S_2") (pintype "bidirectional"))
      (node (ref "Q15") (pin "2") (pinfunction "S_2") (pintype "bidirectional"))
      (node (ref "Q150") (pin "2") (pinfunction "S_2") (pintype "bidirectional"))
      (node (ref "Q151") (pin "2") (pinfunction "S_2") (pintype "bidirectional"))
      (node (ref "Q152") (pin "2") (pinfunction "S_2") (pintype "bidirectional"))
      (node (ref "Q153") (pin "2") (pinfunction "S_2") (pintype "bidirectional"))
      (node (ref "Q154") (pin "2") (pinfunction "S_2") (pintype "bidirectional"))
      (node (ref "Q155") (pin "2") (pinfunction "S_2") (pintype "bidirectional"))
      (node (ref "Q156") (pin "2") (pinfunction "S_2") (pintype "bidirectional"))
      (node (ref "Q157") (pin "2") (pinfunction "S_2") (pintype "bidirectional"))
      (node (ref "Q158") (pin "2") (pinfunction "S_2") (pintype "bidirectional"))
      (node (ref "Q159") (pin "2") (pinfunction "S_2") (pintype "bidirectional"))
      (node (ref "Q16") (pin "2") (pinfunction "S_2") (pintype "bidirectional"))
      (node (ref "Q160") (pin "2") (pinfunction "S_2") (pintype "bidirectional"))
      (node (ref "Q161") (pin "2") (pinfunction "S_2") (pintype "bidirectional"))
      (node (ref "Q162") (pin "2") (pinfunction "S_2") (pintype "bidirectional"))
      (node (ref "Q163") (pin "2") (pinfunction "S_2") (pintype "bidirectional"))
      (node (ref "Q164") (pin "2") (pinfunction "S_2") (pintype "bidirectional"))
      (node (ref "Q165") (pin "2") (pinfunction "S_2") (pintype "bidirectional"))
      (node (ref "Q166") (pin "2") (pinfunction "S_2") (pintype "bidirectional"))
      (node (ref "Q167") (pin "2") (pinfunction "S_2") (pintype "bidirectional"))
      (node (ref "Q168") (pin "2") (pinfunction "S_2") (pintype "bidirectional"))
      (node (ref "Q169") (pin "2") (pinfunction "S_2") (pintype "bidirectional"))
      (node (ref "Q17") (pin "2") (pinfunction "S_2") (pintype "bidirectional"))
      (node (ref "Q170") (pin "2") (pinfunction "S_2") (pintype "bidirectional"))
      (node (ref "Q171") (pin "2") (pinfunction "S_2") (pintype "bidirectional"))
      (node (ref "Q172") (pin "2") (pinfunction "S_2") (pintype "bidirectional"))
      (node (ref "Q173") (pin "2") (pinfunction "S_2") (pintype "bidirectional"))
      (node (ref "Q174") (pin "2") (pinfunction "S_2") (pintype "bidirectional"))
      (node (ref "Q175") (pin "2") (pinfunction "S_2") (pintype "bidirectional"))
      (node (ref "Q176") (pin "2") (pinfunction "S_2") (pintype "bidirectional"))
      (node (ref "Q177") (pin "2") (pinfunction "S_2") (pintype "bidirectional"))
      (node (ref "Q178") (pin "2") (pinfunction "S_2") (pintype "bidirectional"))
      (node (ref "Q179") (pin "2") (pinfunction "S_2") (pintype "bidirectional"))
      (node (ref "Q18") (pin "2") (pinfunction "S_2") (pintype "bidirectional"))
      (node (ref "Q180") (pin "2") (pinfunction "S_2") (pintype "bidirectional"))
      (node (ref "Q181") (pin "2") (pinfunction "S_2") (pintype "bidirectional"))
      (node (ref "Q182") (pin "2") (pinfunction "S_2") (pintype "bidirectional"))
      (node (ref "Q183") (pin "2") (pinfunction "S_2") (pintype "bidirectional"))
      (node (ref "Q19") (pin "2") (pinfunction "S_2") (pintype "bidirectional"))
      (node (ref "Q2") (pin "2") (pinfunction "S_2") (pintype "bidirectional"))
      (node (ref "Q20") (pin "2") (pinfunction "S_2") (pintype "bidirectional"))
      (node (ref "Q21") (pin "2") (pinfunction "S_2") (pintype "bidirectional"))
      (node (ref "Q22") (pin "2") (pinfunction "S_2") (pintype "bidirectional"))
      (node (ref "Q23") (pin "2") (pinfunction "S_2") (pintype "bidirectional"))
      (node (ref "Q24") (pin "2") (pinfunction "S_2") (pintype "bidirectional"))
      (node (ref "Q25") (pin "2") (pinfunction "S_2") (pintype "bidirectional"))
      (node (ref "Q26") (pin "2") (pinfunction "S_2") (pintype "bidirectional"))
      (node (ref "Q27") (pin "2") (pinfunction "S_2") (pintype "bidirectional"))
      (node (ref "Q28") (pin "2") (pinfunction "S_2") (pintype "bidirectional"))
      (node (ref "Q29") (pin "2") (pinfunction "S_2") (pintype "bidirectional"))
      (node (ref "Q3") (pin "2") (pinfunction "S_2") (pintype "bidirectional"))
      (node (ref "Q30") (pin "2") (pinfunction "S_2") (pintype "bidirectional"))
      (node (ref "Q31") (pin "2") (pinfunction "S_2") (pintype "bidirectional"))
      (node (ref "Q32") (pin "2") (pinfunction "S_2") (pintype "bidirectional"))
      (node (ref "Q33") (pin "2") (pinfunction "S_2") (pintype "bidirectional"))
      (node (ref "Q34") (pin "2") (pinfunction "S_2") (pintype "bidirectional"))
      (node (ref "Q35") (pin "2") (pinfunction "S_2") (pintype "bidirectional"))
      (node (ref "Q36") (pin "2") (pinfunction "S_2") (pintype "bidirectional"))
      (node (ref "Q37") (pin "2") (pinfunction "S_2") (pintype "bidirectional"))
      (node (ref "Q38") (pin "2") (pinfunction "S_2") (pintype "bidirectional"))
      (node (ref "Q39") (pin "2") (pinfunction "S_2") (pintype "bidirectional"))
      (node (ref "Q4") (pin "2") (pinfunction "S_2") (pintype "bidirectional"))
      (node (ref "Q40") (pin "2") (pinfunction "S_2") (pintype "bidirectional"))
      (node (ref "Q41") (pin "2") (pinfunction "S_2") (pintype "bidirectional"))
      (node (ref "Q42") (pin "2") (pinfunction "S_2") (pintype "bidirectional"))
      (node (ref "Q43") (pin "2") (pinfunction "S_2") (pintype "bidirectional"))
      (node (ref "Q46") (pin "2") (pinfunction "S_2") (pintype "bidirectional"))
      (node (ref "Q47") (pin "2") (pinfunction "S_2") (pintype "bidirectional"))
      (node (ref "Q48") (pin "2") (pinfunction "S_2") (pintype "bidirectional"))
      (node (ref "Q5") (pin "2") (pinfunction "S_2") (pintype "bidirectional"))
      (node (ref "Q55") (pin "2") (pinfunction "S_2") (pintype "bidirectional"))
      (node (ref "Q56") (pin "2") (pinfunction "S_2") (pintype "bidirectional"))
      (node (ref "Q57") (pin "2") (pinfunction "S_2") (pintype "bidirectional"))
      (node (ref "Q6") (pin "2") (pinfunction "S_2") (pintype "bidirectional"))
      (node (ref "Q61") (pin "2") (pinfunction "S_2") (pintype "bidirectional"))
      (node (ref "Q62") (pin "2") (pinfunction "S_2") (pintype "bidirectional"))
      (node (ref "Q63") (pin "2") (pinfunction "S_2") (pintype "bidirectional"))
      (node (ref "Q67") (pin "2") (pinfunction "S_2") (pintype "bidirectional"))
      (node (ref "Q68") (pin "2") (pinfunction "S_2") (pintype "bidirectional"))
      (node (ref "Q69") (pin "2") (pinfunction "S_2") (pintype "bidirectional"))
      (node (ref "Q7") (pin "2") (pinfunction "S_2") (pintype "bidirectional"))
      (node (ref "Q73") (pin "2") (pinfunction "S_2") (pintype "bidirectional"))
      (node (ref "Q74") (pin "2") (pinfunction "S_2") (pintype "bidirectional"))
      (node (ref "Q75") (pin "2") (pinfunction "S_2") (pintype "bidirectional"))
      (node (ref "Q76") (pin "2") (pinfunction "S_2") (pintype "bidirectional"))
      (node (ref "Q77") (pin "2") (pinfunction "S_2") (pintype "bidirectional"))
      (node (ref "Q78") (pin "2") (pinfunction "S_2") (pintype "bidirectional"))
      (node (ref "Q79") (pin "2") (pinfunction "S_2") (pintype "bidirectional"))
      (node (ref "Q8") (pin "2") (pinfunction "S_2") (pintype "bidirectional"))
      (node (ref "Q80") (pin "2") (pinfunction "S_2") (pintype "bidirectional"))
      (node (ref "Q81") (pin "2") (pinfunction "S_2") (pintype "bidirectional"))
      (node (ref "Q82") (pin "2") (pinfunction "S_2") (pintype "bidirectional"))
      (node (ref "Q83") (pin "2") (pinfunction "S_2") (pintype "bidirectional"))
      (node (ref "Q84") (pin "2") (pinfunction "S_2") (pintype "bidirectional"))
      (node (ref "Q85") (pin "2") (pinfunction "S_2") (pintype "bidirectional"))
      (node (ref "Q86") (pin "2") (pinfunction "S_2") (pintype "bidirectional"))
      (node (ref "Q87") (pin "2") (pinfunction "S_2") (pintype "bidirectional"))
      (node (ref "Q88") (pin "2") (pinfunction "S_2") (pintype "bidirectional"))
      (node (ref "Q89") (pin "2") (pinfunction "S_2") (pintype "bidirectional"))
      (node (ref "Q9") (pin "2") (pinfunction "S_2") (pintype "bidirectional"))
      (node (ref "Q90") (pin "2") (pinfunction "S_2") (pintype "bidirectional"))
      (node (ref "Q91") (pin "2") (pinfunction "S_2") (pintype "bidirectional"))
      (node (ref "Q92") (pin "2") (pinfunction "S_2") (pintype "bidirectional"))
      (node (ref "Q93") (pin "2") (pinfunction "S_2") (pintype "bidirectional"))
      (node (ref "Q94") (pin "2") (pinfunction "S_2") (pintype "bidirectional"))
      (node (ref "Q95") (pin "2") (pinfunction "S_2") (pintype "bidirectional"))
      (node (ref "Q96") (pin "2") (pinfunction "S_2") (pintype "bidirectional"))
      (node (ref "Q97") (pin "2") (pinfunction "S_2") (pintype "bidirectional"))
      (node (ref "Q98") (pin "2") (pinfunction "S_2") (pintype "bidirectional"))
      (node (ref "Q99") (pin "2") (pinfunction "S_2") (pintype "bidirectional"))
      (node (ref "SJ16") (pin "1") (pinfunction "1_1") (pintype "passive"))
      (node (ref "SJ17") (pin "3") (pinfunction "3_3") (pintype "passive"))
    )
    (net (code "19") (name "Net-(Q1-D)") (class "Default")
      (node (ref "Q1") (pin "3") (pinfunction "D_3") (pintype "bidirectional"))
      (node (ref "R17") (pin "1") (pinfunction "1_1") (pintype "passive"))
      (node (ref "SJ13") (pin "3") (pinfunction "3_3") (pintype "passive"))
      (node (ref "SJ14") (pin "3") (pinfunction "3_3") (pintype "passive"))
      (node (ref "SJ15") (pin "3") (pinfunction "3_3") (pintype "passive"))
    )
    (net (code "20") (name "Net-(Q2-D)") (class "Default")
      (node (ref "Q2") (pin "3") (pinfunction "D_3") (pintype "bidirectional"))
      (node (ref "Q39") (pin "3") (pinfunction "D_3") (pintype "bidirectional"))
      (node (ref "Q43") (pin "1") (pinfunction "G_1") (pintype "bidirectional"))
      (node (ref "R19") (pin "1") (pinfunction "1_1") (pintype "passive"))
    )
    (net (code "21") (name "Net-(Q2-G)") (class "Default")
      (node (ref "Q2") (pin "1") (pinfunction "G_1") (pintype "bidirectional"))
      (node (ref "SJ17") (pin "2") (pinfunction "2_2") (pintype "passive"))
    )
    (net (code "22") (name "Net-(Q6-D)") (class "Default")
      (node (ref "Q6") (pin "3") (pinfunction "D_3") (pintype "bidirectional"))
      (node (ref "Q7") (pin "3") (pinfunction "D_3") (pintype "bidirectional"))
      (node (ref "Q8") (pin "1") (pinfunction "G_1") (pintype "bidirectional"))
      (node (ref "R3") (pin "1") (pinfunction "1_1") (pintype "passive"))
    )
    (net (code "23") (name "Net-(Q10-D)") (class "Default")
      (node (ref "Q10") (pin "3") (pinfunction "D_3") (pintype "bidirectional"))
      (node (ref "Q12") (pin "1") (pinfunction "G_1") (pintype "bidirectional"))
      (node (ref "Q19") (pin "3") (pinfunction "D_3") (pintype "bidirectional"))
      (node (ref "Q5") (pin "3") (pinfunction "D_3") (pintype "bidirectional"))
      (node (ref "Q9") (pin "1") (pinfunction "G_1") (pintype "bidirectional"))
      (node (ref "R2") (pin "1") (pinfunction "1_1") (pintype "passive"))
    )
    (net (code "24") (name "Net-(Q10-G)") (class "Default")
      (node (ref "Q10") (pin "1") (pinfunction "G_1") (pintype "bidirectional"))
      (node (ref "Q3") (pin "3") (pinfunction "D_3") (pintype "bidirectional"))
      (node (ref "Q4") (pin "3") (pinfunction "D_3") (pintype "bidirectional"))
      (node (ref "R1") (pin "1") (pinfunction "1_1") (pintype "passive"))
    )
    (net (code "25") (name "Net-(Q11-D)") (class "Default")
      (node (ref "Q11") (pin "3") (pinfunction "D_3") (pintype "bidirectional"))
      (node (ref "Q12") (pin "3") (pinfunction "D_3") (pintype "bidirectional"))
      (node (ref "Q18") (pin "1") (pinfunction "G_1") (pintype "bidirectional"))
      (node (ref "R5") (pin "1") (pinfunction "1_1") (pintype "passive"))
    )
    (net (code "26") (name "Net-(Q14-D)") (class "Default")
      (node (ref "Q14") (pin "3") (pinfunction "D_3") (pintype "bidirectional"))
      (node (ref "Q15") (pin "3") (pinfunction "D_3") (pintype "bidirectional"))
      (node (ref "Q16") (pin "1") (pinfunction "G_1") (pintype "bidirectional"))
      (node (ref "R7") (pin "1") (pinfunction "1_1") (pintype "passive"))
    )
    (net (code "27") (name "Net-(Q15-G)") (class "Default")
      (node (ref "Q15") (pin "1") (pinfunction "G_1") (pintype "bidirectional"))
      (node (ref "Q5") (pin "1") (pinfunction "G_1") (pintype "bidirectional"))
      (node (ref "Q8") (pin "3") (pinfunction "D_3") (pintype "bidirectional"))
      (node (ref "Q9") (pin "3") (pinfunction "D_3") (pintype "bidirectional"))
      (node (ref "R4") (pin "1") (pinfunction "1_1") (pintype "passive"))
    )
    (net (code "28") (name "Net-(Q21-D)") (class "Default")
      (node (ref "Q21") (pin "3") (pinfunction "D_3") (pintype "bidirectional"))
      (node (ref "Q22") (pin "3") (pinfunction "D_3") (pintype "bidirectional"))
      (node (ref "Q28") (pin "1") (pinfunction "G_1") (pintype "bidirectional"))
      (node (ref "R9") (pin "1") (pinfunction "1_1") (pintype "passive"))
    )
    (net (code "29") (name "Net-(Q23-D)") (class "Default")
      (node (ref "Q23") (pin "3") (pinfunction "D_3") (pintype "bidirectional"))
      (node (ref "Q27") (pin "1") (pinfunction "G_1") (pintype "bidirectional"))
      (node (ref "Q28") (pin "3") (pinfunction "D_3") (pintype "bidirectional"))
      (node (ref "Q30") (pin "1") (pinfunction "G_1") (pintype "bidirectional"))
      (node (ref "Q37") (pin "3") (pinfunction "D_3") (pintype "bidirectional"))
      (node (ref "R10") (pin "1") (pinfunction "1_1") (pintype "passive"))
    )
    (net (code "30") (name "Net-(Q23-G)") (class "Default")
      (node (ref "Q23") (pin "1") (pinfunction "G_1") (pintype "bidirectional"))
      (node (ref "Q26") (pin "3") (pinfunction "D_3") (pintype "bidirectional"))
      (node (ref "Q27") (pin "3") (pinfunction "D_3") (pintype "bidirectional"))
      (node (ref "Q33") (pin "1") (pinfunction "G_1") (pintype "bidirectional"))
      (node (ref "R12") (pin "1") (pinfunction "1_1") (pintype "passive"))
    )
    (net (code "31") (name "Net-(Q24-D)") (class "Default")
      (node (ref "Q24") (pin "3") (pinfunction "D_3") (pintype "bidirectional"))
      (node (ref "Q25") (pin "3") (pinfunction "D_3") (pintype "bidirectional"))
      (node (ref "Q26") (pin "1") (pinfunction "G_1") (pintype "bidirectional"))
      (node (ref "R11") (pin "1") (pinfunction "1_1") (pintype "passive"))
    )
    (net (code "32") (name "Net-(Q29-D)") (class "Default")
      (node (ref "Q29") (pin "3") (pinfunction "D_3") (pintype "bidirectional"))
      (node (ref "Q30") (pin "3") (pinfunction "D_3") (pintype "bidirectional"))
      (node (ref "Q36") (pin "1") (pinfunction "G_1") (pintype "bidirectional"))
      (node (ref "R13") (pin "1") (pinfunction "1_1") (pintype "passive"))
    )
    (net (code "33") (name "Net-(Q32-D)") (class "Default")
      (node (ref "Q32") (pin "3") (pinfunction "D_3") (pintype "bidirectional"))
      (node (ref "Q33") (pin "3") (pinfunction "D_3") (pintype "bidirectional"))
      (node (ref "Q34") (pin "1") (pinfunction "G_1") (pintype "bidirectional"))
      (node (ref "R15") (pin "1") (pinfunction "1_1") (pintype "passive"))
    )
    (net (code "34") (name "Net-(Q73-D)") (class "Default")
      (node (ref "Q73") (pin "3") (pinfunction "D_3") (pintype "bidirectional"))
      (node (ref "Q74") (pin "3") (pinfunction "D_3") (pintype "bidirectional"))
      (node (ref "Q80") (pin "1") (pinfunction "G_1") (pintype "bidirectional"))
      (node (ref "R33") (pin "1") (pinfunction "1_1") (pintype "passive"))
    )
    (net (code "35") (name "Net-(Q75-D)") (class "Default")
      (node (ref "Q75") (pin "3") (pinfunction "D_3") (pintype "bidirectional"))
      (node (ref "Q79") (pin "1") (pinfunction "G_1") (pintype "bidirectional"))
      (node (ref "Q80") (pin "3") (pinfunction "D_3") (pintype "bidirectional"))
      (node (ref "Q82") (pin "1") (pinfunction "G_1") (pintype "bidirectional"))
      (node (ref "Q89") (pin "3") (pinfunction "D_3") (pintype "bidirectional"))
      (node (ref "R34") (pin "1") (pinfunction "1_1") (pintype "passive"))
    )
    (net (code "36") (name "Net-(Q75-G)") (class "Default")
      (node (ref "Q75") (pin "1") (pinfunction "G_1") (pintype "bidirectional"))
      (node (ref "Q78") (pin "3") (pinfunction "D_3") (pintype "bidirectional"))
      (node (ref "Q79") (pin "3") (pinfunction "D_3") (pintype "bidirectional"))
      (node (ref "Q85") (pin "1") (pinfunction "G_1") (pintype "bidirectional"))
      (node (ref "R36") (pin "1") (pinfunction "1_1") (pintype "passive"))
    )
    (net (code "37") (name "Net-(Q76-D)") (class "Default")
      (node (ref "Q76") (pin "3") (pinfunction "D_3") (pintype "bidirectional"))
      (node (ref "Q77") (pin "3") (pinfunction "D_3") (pintype "bidirectional"))
      (node (ref "Q78") (pin "1") (pinfunction "G_1") (pintype "bidirectional"))
      (node (ref "R35") (pin "1") (pinfunction "1_1") (pintype "passive"))
    )
    (net (code "38") (name "Net-(Q81-D)") (class "Default")
      (node (ref "Q81") (pin "3") (pinfunction "D_3") (pintype "bidirectional"))
      (node (ref "Q82") (pin "3") (pinfunction "D_3") (pintype "bidirectional"))
      (node (ref "Q88") (pin "1") (pinfunction "G_1") (pintype "bidirectional"))
      (node (ref "R37") (pin "1") (pinfunction "1_1") (pintype "passive"))
    )
    (net (code "39") (name "Net-(Q84-D)") (class "Default")
      (node (ref "Q84") (pin "3") (pinfunction "D_3") (pintype "bidirectional"))
      (node (ref "Q85") (pin "3") (pinfunction "D_3") (pintype "bidirectional"))
      (node (ref "Q86") (pin "1") (pinfunction "G_1") (pintype "bidirectional"))
      (node (ref "R39") (pin "1") (pinfunction "1_1") (pintype "passive"))
    )
    (net (code "40") (name "Net-(Q91-D)") (class "Default")
      (node (ref "Q91") (pin "3") (pinfunction "D_3") (pintype "bidirectional"))
      (node (ref "Q92") (pin "3") (pinfunction "D_3") (pintype "bidirectional"))
      (node (ref "Q98") (pin "1") (pinfunction "G_1") (pintype "bidirectional"))
      (node (ref "R41") (pin "1") (pinfunction "1_1") (pintype "passive"))
    )
    (net (code "41") (name "Net-(Q94-D)") (class "Default")
      (node (ref "Q94") (pin "3") (pinfunction "D_3") (pintype "bidirectional"))
      (node (ref "Q95") (pin "3") (pinfunction "D_3") (pintype "bidirectional"))
      (node (ref "Q96") (pin "1") (pinfunction "G_1") (pintype "bidirectional"))
      (node (ref "R43") (pin "1") (pinfunction "1_1") (pintype "passive"))
    )
    (net (code "42") (name "Net-(Q100-D)") (class "Default")
      (node (ref "Q100") (pin "3") (pinfunction "D_3") (pintype "bidirectional"))
      (node (ref "Q106") (pin "1") (pinfunction "G_1") (pintype "bidirectional"))
      (node (ref "Q99") (pin "3") (pinfunction "D_3") (pintype "bidirectional"))
      (node (ref "R45") (pin "1") (pinfunction "1_1") (pintype "passive"))
    )
    (net (code "43") (name "Net-(Q100-G)") (class "Default")
      (node (ref "Q100") (pin "1") (pinfunction "G_1") (pintype "bidirectional"))
      (node (ref "Q107") (pin "3") (pinfunction "D_3") (pintype "bidirectional"))
      (node (ref "Q93") (pin "3") (pinfunction "D_3") (pintype "bidirectional"))
      (node (ref "Q97") (pin "1") (pinfunction "G_1") (pintype "bidirectional"))
      (node (ref "Q98") (pin "3") (pinfunction "D_3") (pintype "bidirectional"))
      (node (ref "R42") (pin "1") (pinfunction "1_1") (pintype "passive"))
    )
    (net (code "44") (name "Net-(Q102-D)") (class "Default")
      (node (ref "Q102") (pin "3") (pinfunction "D_3") (pintype "bidirectional"))
      (node (ref "Q103") (pin "3") (pinfunction "D_3") (pintype "bidirectional"))
      (node (ref "Q104") (pin "1") (pinfunction "G_1") (pintype "bidirectional"))
      (node (ref "R47") (pin "1") (pinfunction "1_1") (pintype "passive"))
    )
    (net (code "45") (name "Net-(Q103-G)") (class "Default")
      (node (ref "Q103") (pin "1") (pinfunction "G_1") (pintype "bidirectional"))
      (node (ref "Q93") (pin "1") (pinfunction "G_1") (pintype "bidirectional"))
      (node (ref "Q96") (pin "3") (pinfunction "D_3") (pintype "bidirectional"))
      (node (ref "Q97") (pin "3") (pinfunction "D_3") (pintype "bidirectional"))
      (node (ref "R44") (pin "1") (pinfunction "1_1") (pintype "passive"))
    )
    (net (code "46") (name "Net-(Q145-D)") (class "Default")
      (node (ref "Q145") (pin "3") (pinfunction "D_3") (pintype "bidirectional"))
      (node (ref "Q146") (pin "3") (pinfunction "D_3") (pintype "bidirectional"))
      (node (ref "Q152") (pin "1") (pinfunction "G_1") (pintype "bidirectional"))
      (node (ref "R65") (pin "1") (pinfunction "1_1") (pintype "passive"))
    )
    (net (code "47") (name "Net-(Q147-D)") (class "Default")
      (node (ref "Q147") (pin "3") (pinfunction "D_3") (pintype "bidirectional"))
      (node (ref "Q151") (pin "1") (pinfunction "G_1") (pintype "bidirectional"))
      (node (ref "Q152") (pin "3") (pinfunction "D_3") (pintype "bidirectional"))
      (node (ref "Q154") (pin "1") (pinfunction "G_1") (pintype "bidirectional"))
      (node (ref "Q161") (pin "3") (pinfunction "D_3") (pintype "bidirectional"))
      (node (ref "R66") (pin "1") (pinfunction "1_1") (pintype "passive"))
    )
    (net (code "48") (name "Net-(Q147-G)") (class "Default")
      (node (ref "Q147") (pin "1") (pinfunction "G_1") (pintype "bidirectional"))
      (node (ref "Q150") (pin "3") (pinfunction "D_3") (pintype "bidirectional"))
      (node (ref "Q151") (pin "3") (pinfunction "D_3") (pintype "bidirectional"))
      (node (ref "Q157") (pin "1") (pinfunction "G_1") (pintype "bidirectional"))
      (node (ref "R68") (pin "1") (pinfunction "1_1") (pintype "passive"))
    )
    (net (code "49") (name "Net-(Q148-D)") (class "Default")
      (node (ref "Q148") (pin "3") (pinfunction "D_3") (pintype "bidirectional"))
      (node (ref "Q149") (pin "3") (pinfunction "D_3") (pintype "bidirectional"))
      (node (ref "Q150") (pin "1") (pinfunction "G_1") (pintype "bidirectional"))
      (node (ref "R67") (pin "1") (pinfunction "1_1") (pintype "passive"))
    )
    (net (code "50") (name "Net-(Q153-D)") (class "Default")
      (node (ref "Q153") (pin "3") (pinfunction "D_3") (pintype "bidirectional"))
      (node (ref "Q154") (pin "3") (pinfunction "D_3") (pintype "bidirectional"))
      (node (ref "Q160") (pin "1") (pinfunction "G_1") (pintype "bidirectional"))
      (node (ref "R69") (pin "1") (pinfunction "1_1") (pintype "passive"))
    )
    (net (code "51") (name "Net-(Q156-D)") (class "Default")
      (node (ref "Q156") (pin "3") (pinfunction "D_3") (pintype "bidirectional"))
      (node (ref "Q157") (pin "3") (pinfunction "D_3") (pintype "bidirectional"))
      (node (ref "Q158") (pin "1") (pinfunction "G_1") (pintype "bidirectional"))
      (node (ref "R71") (pin "1") (pinfunction "1_1") (pintype "passive"))
    )
    (net (code "52") (name "Net-(Q163-D)") (class "Default")
      (node (ref "Q163") (pin "3") (pinfunction "D_3") (pintype "bidirectional"))
      (node (ref "Q164") (pin "3") (pinfunction "D_3") (pintype "bidirectional"))
      (node (ref "Q170") (pin "1") (pinfunction "G_1") (pintype "bidirectional"))
      (node (ref "R73") (pin "1") (pinfunction "1_1") (pintype "passive"))
    )
    (net (code "53") (name "Net-(Q165-D)") (class "Default")
      (node (ref "Q165") (pin "3") (pinfunction "D_3") (pintype "bidirectional"))
      (node (ref "Q169") (pin "1") (pinfunction "G_1") (pintype "bidirectional"))
      (node (ref "Q170") (pin "3") (pinfunction "D_3") (pintype "bidirectional"))
      (node (ref "Q172") (pin "1") (pinfunction "G_1") (pintype "bidirectional"))
      (node (ref "Q179") (pin "3") (pinfunction "D_3") (pintype "bidirectional"))
      (node (ref "R74") (pin "1") (pinfunction "1_1") (pintype "passive"))
    )
    (net (code "54") (name "Net-(Q165-G)") (class "Default")
      (node (ref "Q165") (pin "1") (pinfunction "G_1") (pintype "bidirectional"))
      (node (ref "Q168") (pin "3") (pinfunction "D_3") (pintype "bidirectional"))
      (node (ref "Q169") (pin "3") (pinfunction "D_3") (pintype "bidirectional"))
      (node (ref "Q175") (pin "1") (pinfunction "G_1") (pintype "bidirectional"))
      (node (ref "R76") (pin "1") (pinfunction "1_1") (pintype "passive"))
    )
    (net (code "55") (name "Net-(Q166-D)") (class "Default")
      (node (ref "Q166") (pin "3") (pinfunction "D_3") (pintype "bidirectional"))
      (node (ref "Q167") (pin "3") (pinfunction "D_3") (pintype "bidirectional"))
      (node (ref "Q168") (pin "1") (pinfunction "G_1") (pintype "bidirectional"))
      (node (ref "R75") (pin "1") (pinfunction "1_1") (pintype "passive"))
    )
    (net (code "56") (name "Net-(Q171-D)") (class "Default")
      (node (ref "Q171") (pin "3") (pinfunction "D_3") (pintype "bidirectional"))
      (node (ref "Q172") (pin "3") (pinfunction "D_3") (pintype "bidirectional"))
      (node (ref "Q178") (pin "1") (pinfunction "G_1") (pintype "bidirectional"))
      (node (ref "R77") (pin "1") (pinfunction "1_1") (pintype "passive"))
    )
    (net (code "57") (name "Net-(Q174-D)") (class "Default")
      (node (ref "Q174") (pin "3") (pinfunction "D_3") (pintype "bidirectional"))
      (node (ref "Q175") (pin "3") (pinfunction "D_3") (pintype "bidirectional"))
      (node (ref "Q176") (pin "1") (pinfunction "G_1") (pintype "bidirectional"))
      (node (ref "R79") (pin "1") (pinfunction "1_1") (pintype "passive"))
    )
    (net (code "58") (name "Net-(SJ1-Pad1)") (class "Default")
      (node (ref "SJ1") (pin "1") (pinfunction "1_1") (pintype "passive"))
      (node (ref "SJ10") (pin "1") (pinfunction "1_1") (pintype "passive"))
      (node (ref "SJ11") (pin "1") (pinfunction "1_1") (pintype "passive"))
      (node (ref "SJ12") (pin "1") (pinfunction "1_1") (pintype "passive"))
      (node (ref "SJ16") (pin "2") (pinfunction "2_2") (pintype "passive"))
      (node (ref "SJ2") (pin "1") (pinfunction "1_1") (pintype "passive"))
      (node (ref "SJ3") (pin "1") (pinfunction "1_1") (pintype "passive"))
      (node (ref "SJ4") (pin "1") (pinfunction "1_1") (pintype "passive"))
      (node (ref "SJ5") (pin "1") (pinfunction "1_1") (pintype "passive"))
      (node (ref "SJ6") (pin "1") (pinfunction "1_1") (pintype "passive"))
      (node (ref "SJ7") (pin "1") (pinfunction "1_1") (pintype "passive"))
      (node (ref "SJ8") (pin "1") (pinfunction "1_1") (pintype "passive"))
      (node (ref "SJ9") (pin "1") (pinfunction "1_1") (pintype "passive"))
    )
    (net (code "59") (name "Net-(SJ15-Pad2)") (class "Default")
      (node (ref "SJ15") (pin "2") (pinfunction "2_2") (pintype "passive"))
      (node (ref "SJ16") (pin "3") (pinfunction "3_3") (pintype "passive"))
    )
    (net (code "60") (name "O0") (class "Default")
      (node (ref "JP1") (pin "1") (pinfunction "1_1") (pintype "passive"))
      (node (ref "Q40") (pin "3") (pinfunction "D_3") (pintype "bidirectional"))
      (node (ref "Q41") (pin "3") (pinfunction "D_3") (pintype "bidirectional"))
      (node (ref "Q42") (pin "3") (pinfunction "D_3") (pintype "bidirectional"))
      (node (ref "R18") (pin "1") (pinfunction "1_1") (pintype "passive"))
      (node (ref "SJ2") (pin "3") (pinfunction "3_3") (pintype "passive"))
    )
    (net (code "61") (name "O1") (class "Default")
      (node (ref "JP1") (pin "2") (pinfunction "2_2") (pintype "passive"))
      (node (ref "Q46") (pin "3") (pinfunction "D_3") (pintype "bidirectional"))
      (node (ref "Q47") (pin "3") (pinfunction "D_3") (pintype "bidirectional"))
      (node (ref "Q48") (pin "3") (pinfunction "D_3") (pintype "bidirectional"))
      (node (ref "R20") (pin "1") (pinfunction "1_1") (pintype "passive"))
      (node (ref "SJ3") (pin "3") (pinfunction "3_3") (pintype "passive"))
    )
    (net (code "62") (name "O2") (class "Default")
      (node (ref "JP1") (pin "3") (pinfunction "3_3") (pintype "passive"))
      (node (ref "Q55") (pin "3") (pinfunction "D_3") (pintype "bidirectional"))
      (node (ref "Q56") (pin "3") (pinfunction "D_3") (pintype "bidirectional"))
      (node (ref "Q57") (pin "3") (pinfunction "D_3") (pintype "bidirectional"))
      (node (ref "R23") (pin "1") (pinfunction "1_1") (pintype "passive"))
      (node (ref "SJ4") (pin "3") (pinfunction "3_3") (pintype "passive"))
    )
    (net (code "63") (name "O3") (class "Default")
      (node (ref "JP1") (pin "4") (pinfunction "4_4") (pintype "passive"))
      (node (ref "Q61") (pin "3") (pinfunction "D_3") (pintype "bidirectional"))
      (node (ref "Q62") (pin "3") (pinfunction "D_3") (pintype "bidirectional"))
      (node (ref "Q63") (pin "3") (pinfunction "D_3") (pintype "bidirectional"))
      (node (ref "R25") (pin "1") (pinfunction "1_1") (pintype "passive"))
      (node (ref "SJ5") (pin "3") (pinfunction "3_3") (pintype "passive"))
    )
    (net (code "64") (name "O4") (class "Default")
      (node (ref "JP1") (pin "5") (pinfunction "5_5") (pintype "passive"))
      (node (ref "Q67") (pin "3") (pinfunction "D_3") (pintype "bidirectional"))
      (node (ref "Q68") (pin "3") (pinfunction "D_3") (pintype "bidirectional"))
      (node (ref "Q69") (pin "3") (pinfunction "D_3") (pintype "bidirectional"))
      (node (ref "R27") (pin "1") (pinfunction "1_1") (pintype "passive"))
      (node (ref "SJ6") (pin "3") (pinfunction "3_3") (pintype "passive"))
    )
    (net (code "65") (name "O5") (class "Default")
      (node (ref "JP1") (pin "6") (pinfunction "6_6") (pintype "passive"))
      (node (ref "Q109") (pin "3") (pinfunction "D_3") (pintype "bidirectional"))
      (node (ref "Q110") (pin "3") (pinfunction "D_3") (pintype "bidirectional"))
      (node (ref "Q111") (pin "3") (pinfunction "D_3") (pintype "bidirectional"))
      (node (ref "R29") (pin "1") (pinfunction "1_1") (pintype "passive"))
      (node (ref "SJ7") (pin "3") (pinfunction "3_3") (pintype "passive"))
    )
    (net (code "66") (name "O6") (class "Default")
      (node (ref "JP1") (pin "7") (pinfunction "7_7") (pintype "passive"))
      (node (ref "Q115") (pin "3") (pinfunction "D_3") (pintype "bidirectional"))
      (node (ref "Q116") (pin "3") (pinfunction "D_3") (pintype "bidirectional"))
      (node (ref "Q117") (pin "3") (pinfunction "D_3") (pintype "bidirectional"))
      (node (ref "R31") (pin "1") (pinfunction "1_1") (pintype "passive"))
      (node (ref "SJ8") (pin "3") (pinfunction "3_3") (pintype "passive"))
    )
    (net (code "67") (name "O7") (class "Default")
      (node (ref "JP1") (pin "8") (pinfunction "8_8") (pintype "passive"))
      (node (ref "Q121") (pin "3") (pinfunction "D_3") (pintype "bidirectional"))
      (node (ref "Q122") (pin "3") (pinfunction "D_3") (pintype "bidirectional"))
      (node (ref "Q123") (pin "3") (pinfunction "D_3") (pintype "bidirectional"))
      (node (ref "R49") (pin "1") (pinfunction "1_1") (pintype "passive"))
      (node (ref "SJ9") (pin "3") (pinfunction "3_3") (pintype "passive"))
    )
    (net (code "68") (name "O8") (class "Default")
      (node (ref "JP1") (pin "9") (pinfunction "9_9") (pintype "passive"))
      (node (ref "Q127") (pin "3") (pinfunction "D_3") (pintype "bidirectional"))
      (node (ref "Q128") (pin "3") (pinfunction "D_3") (pintype "bidirectional"))
      (node (ref "Q129") (pin "3") (pinfunction "D_3") (pintype "bidirectional"))
      (node (ref "R51") (pin "1") (pinfunction "1_1") (pintype "passive"))
      (node (ref "SJ10") (pin "3") (pinfunction "3_3") (pintype "passive"))
    )
    (net (code "69") (name "O9") (class "Default")
      (node (ref "JP1") (pin "10") (pinfunction "10_10") (pintype "passive"))
      (node (ref "Q133") (pin "3") (pinfunction "D_3") (pintype "bidirectional"))
      (node (ref "Q134") (pin "3") (pinfunction "D_3") (pintype "bidirectional"))
      (node (ref "Q135") (pin "3") (pinfunction "D_3") (pintype "bidirectional"))
      (node (ref "R53") (pin "1") (pinfunction "1_1") (pintype "passive"))
      (node (ref "SJ11") (pin "3") (pinfunction "3_3") (pintype "passive"))
    )
    (net (code "70") (name "O10") (class "Default")
      (node (ref "JP1") (pin "11") (pinfunction "11_11") (pintype "passive"))
      (node (ref "Q139") (pin "3") (pinfunction "D_3") (pintype "bidirectional"))
      (node (ref "Q140") (pin "3") (pinfunction "D_3") (pintype "bidirectional"))
      (node (ref "Q141") (pin "3") (pinfunction "D_3") (pintype "bidirectional"))
      (node (ref "R55") (pin "1") (pinfunction "1_1") (pintype "passive"))
      (node (ref "SJ12") (pin "3") (pinfunction "3_3") (pintype "passive"))
    )
    (net (code "71") (name "O11") (class "Default")
      (node (ref "JP1") (pin "12") (pinfunction "12_12") (pintype "passive"))
      (node (ref "Q181") (pin "3") (pinfunction "D_3") (pintype "bidirectional"))
      (node (ref "Q182") (pin "3") (pinfunction "D_3") (pintype "bidirectional"))
      (node (ref "Q183") (pin "3") (pinfunction "D_3") (pintype "bidirectional"))
      (node (ref "R57") (pin "1") (pinfunction "1_1") (pintype "passive"))
      (node (ref "SJ1") (pin "3") (pinfunction "3_3") (pintype "passive"))
    )
    (net (code "72") (name "Q0") (class "Default")
      (node (ref "Q121") (pin "1") (pinfunction "G_1") (pintype "bidirectional"))
      (node (ref "Q13") (pin "3") (pinfunction "D_3") (pintype "bidirectional"))
      (node (ref "Q17") (pin "1") (pinfunction "G_1") (pintype "bidirectional"))
      (node (ref "Q18") (pin "3") (pinfunction "D_3") (pintype "bidirectional"))
      (node (ref "Q20") (pin "3") (pinfunction "D_3") (pintype "bidirectional"))
      (node (ref "Q22") (pin "1") (pinfunction "G_1") (pintype "bidirectional"))
      (node (ref "Q40") (pin "1") (pinfunction "G_1") (pintype "bidirectional"))
      (node (ref "R6") (pin "1") (pinfunction "1_1") (pintype "passive"))
    )
    (net (code "73") (name "Q1") (class "Default")
      (node (ref "Q127") (pin "1") (pinfunction "G_1") (pintype "bidirectional"))
      (node (ref "Q31") (pin "3") (pinfunction "D_3") (pintype "bidirectional"))
      (node (ref "Q35") (pin "1") (pinfunction "G_1") (pintype "bidirectional"))
      (node (ref "Q36") (pin "3") (pinfunction "D_3") (pintype "bidirectional"))
      (node (ref "Q38") (pin "3") (pinfunction "D_3") (pintype "bidirectional"))
      (node (ref "Q47") (pin "1") (pinfunction "G_1") (pintype "bidirectional"))
      (node (ref "Q74") (pin "1") (pinfunction "G_1") (pintype "bidirectional"))
      (node (ref "R14") (pin "1") (pinfunction "1_1") (pintype "passive"))
    )
    (net (code "74") (name "Q2") (class "Default")
      (node (ref "Q133") (pin "1") (pinfunction "G_1") (pintype "bidirectional"))
      (node (ref "Q56") (pin "1") (pinfunction "G_1") (pintype "bidirectional"))
      (node (ref "Q83") (pin "3") (pinfunction "D_3") (pintype "bidirectional"))
      (node (ref "Q87") (pin "1") (pinfunction "G_1") (pintype "bidirectional"))
      (node (ref "Q88") (pin "3") (pinfunction "D_3") (pintype "bidirectional"))
      (node (ref "Q90") (pin "3") (pinfunction "D_3") (pintype "bidirectional"))
      (node (ref "Q92") (pin "1") (pinfunction "G_1") (pintype "bidirectional"))
      (node (ref "R38") (pin "1") (pinfunction "1_1") (pintype "passive"))
    )
    (net (code "75") (name "Q3") (class "Default")
      (node (ref "Q101") (pin "3") (pinfunction "D_3") (pintype "bidirectional"))
      (node (ref "Q105") (pin "1") (pinfunction "G_1") (pintype "bidirectional"))
      (node (ref "Q106") (pin "3") (pinfunction "D_3") (pintype "bidirectional"))
      (node (ref "Q108") (pin "3") (pinfunction "D_3") (pintype "bidirectional"))
      (node (ref "Q139") (pin "1") (pinfunction "G_1") (pintype "bidirectional"))
      (node (ref "Q146") (pin "1") (pinfunction "G_1") (pintype "bidirectional"))
      (node (ref "Q62") (pin "1") (pinfunction "G_1") (pintype "bidirectional"))
      (node (ref "R46") (pin "1") (pinfunction "1_1") (pintype "passive"))
    )
    (net (code "76") (name "Q4") (class "Default")
      (node (ref "Q155") (pin "3") (pinfunction "D_3") (pintype "bidirectional"))
      (node (ref "Q159") (pin "1") (pinfunction "G_1") (pintype "bidirectional"))
      (node (ref "Q160") (pin "3") (pinfunction "D_3") (pintype "bidirectional"))
      (node (ref "Q162") (pin "3") (pinfunction "D_3") (pintype "bidirectional"))
      (node (ref "Q164") (pin "1") (pinfunction "G_1") (pintype "bidirectional"))
      (node (ref "Q181") (pin "1") (pinfunction "G_1") (pintype "bidirectional"))
      (node (ref "Q68") (pin "1") (pinfunction "G_1") (pintype "bidirectional"))
      (node (ref "R70") (pin "1") (pinfunction "1_1") (pintype "passive"))
    )
    (net (code "77") (name "Q5") (class "Default")
      (node (ref "Q110") (pin "1") (pinfunction "G_1") (pintype "bidirectional"))
      (node (ref "Q173") (pin "3") (pinfunction "D_3") (pintype "bidirectional"))
      (node (ref "Q177") (pin "1") (pinfunction "G_1") (pintype "bidirectional"))
      (node (ref "Q178") (pin "3") (pinfunction "D_3") (pintype "bidirectional"))
      (node (ref "Q180") (pin "3") (pinfunction "D_3") (pintype "bidirectional"))
      (node (ref "Q41") (pin "1") (pinfunction "G_1") (pintype "bidirectional"))
      (node (ref "Q7") (pin "1") (pinfunction "G_1") (pintype "bidirectional"))
      (node (ref "R78") (pin "1") (pinfunction "1_1") (pintype "passive"))
    )
    (net (code "78") (name "VCC") (class "Default")
      (node (ref "C1") (pin "1") (pinfunction "1_1") (pintype "passive"))
      (node (ref "JP1") (pin "29") (pinfunction "29_29") (pintype "passive"))
      (node (ref "R1") (pin "2") (pinfunction "2_2") (pintype "passive"))
      (node (ref "R10") (pin "2") (pinfunction "2_2") (pintype "passive"))
      (node (ref "R11") (pin "2") (pinfunction "2_2") (pintype "passive"))
      (node (ref "R12") (pin "2") (pinfunction "2_2") (pintype "passive"))
      (node (ref "R13") (pin "2") (pinfunction "2_2") (pintype "passive"))
      (node (ref "R14") (pin "2") (pinfunction "2_2") (pintype "passive"))
      (node (ref "R15") (pin "2") (pinfunction "2_2") (pintype "passive"))
      (node (ref "R16") (pin "2") (pinfunction "2_2") (pintype "passive"))
      (node (ref "R17") (pin "2") (pinfunction "2_2") (pintype "passive"))
      (node (ref "R18") (pin "2") (pinfunction "2_2") (pintype "passive"))
      (node (ref "R19") (pin "2") (pinfunction "2_2") (pintype "passive"))
      (node (ref "R2") (pin "2") (pinfunction "2_2") (pintype "passive"))
      (node (ref "R20") (pin "2") (pinfunction "2_2") (pintype "passive"))
      (node (ref "R21") (pin "2") (pinfunction "2_2") (pintype "passive"))
      (node (ref "R23") (pin "2") (pinfunction "2_2") (pintype "passive"))
      (node (ref "R25") (pin "2") (pinfunction "2_2") (pintype "passive"))
      (node (ref "R27") (pin "2") (pinfunction "2_2") (pintype "passive"))
      (node (ref "R29") (pin "2") (pinfunction "2_2") (pintype "passive"))
      (node (ref "R3") (pin "2") (pinfunction "2_2") (pintype "passive"))
      (node (ref "R31") (pin "2") (pinfunction "2_2") (pintype "passive"))
      (node (ref "R33") (pin "2") (pinfunction "2_2") (pintype "passive"))
      (node (ref "R34") (pin "2") (pinfunction "2_2") (pintype "passive"))
      (node (ref "R35") (pin "2") (pinfunction "2_2") (pintype "passive"))
      (node (ref "R36") (pin "2") (pinfunction "2_2") (pintype "passive"))
      (node (ref "R37") (pin "2") (pinfunction "2_2") (pintype "passive"))
      (node (ref "R38") (pin "2") (pinfunction "2_2") (pintype "passive"))
      (node (ref "R39") (pin "2") (pinfunction "2_2") (pintype "passive"))
      (node (ref "R4") (pin "2") (pinfunction "2_2") (pintype "passive"))
      (node (ref "R40") (pin "2") (pinfunction "2_2") (pintype "passive"))
      (node (ref "R41") (pin "2") (pinfunction "2_2") (pintype "passive"))
      (node (ref "R42") (pin "2") (pinfunction "2_2") (pintype "passive"))
      (node (ref "R43") (pin "2") (pinfunction "2_2") (pintype "passive"))
      (node (ref "R44") (pin "2") (pinfunction "2_2") (pintype "passive"))
      (node (ref "R45") (pin "2") (pinfunction "2_2") (pintype "passive"))
      (node (ref "R46") (pin "2") (pinfunction "2_2") (pintype "passive"))
      (node (ref "R47") (pin "2") (pinfunction "2_2") (pintype "passive"))
      (node (ref "R48") (pin "2") (pinfunction "2_2") (pintype "passive"))
      (node (ref "R49") (pin "2") (pinfunction "2_2") (pintype "passive"))
      (node (ref "R5") (pin "2") (pinfunction "2_2") (pintype "passive"))
      (node (ref "R51") (pin "2") (pinfunction "2_2") (pintype "passive"))
      (node (ref "R53") (pin "2") (pinfunction "2_2") (pintype "passive"))
      (node (ref "R55") (pin "2") (pinfunction "2_2") (pintype "passive"))
      (node (ref "R57") (pin "2") (pinfunction "2_2") (pintype "passive"))
      (node (ref "R6") (pin "2") (pinfunction "2_2") (pintype "passive"))
      (node (ref "R65") (pin "2") (pinfunction "2_2") (pintype "passive"))
      (node (ref "R66") (pin "2") (pinfunction "2_2") (pintype "passive"))
      (node (ref "R67") (pin "2") (pinfunction "2_2") (pintype "passive"))
      (node (ref "R68") (pin "2") (pinfunction "2_2") (pintype "passive"))
      (node (ref "R69") (pin "2") (pinfunction "2_2") (pintype "passive"))
      (node (ref "R7") (pin "2") (pinfunction "2_2") (pintype "passive"))
      (node (ref "R70") (pin "2") (pinfunction "2_2") (pintype "passive"))
      (node (ref "R71") (pin "2") (pinfunction "2_2") (pintype "passive"))
      (node (ref "R72") (pin "2") (pinfunction "2_2") (pintype "passive"))
      (node (ref "R73") (pin "2") (pinfunction "2_2") (pintype "passive"))
      (node (ref "R74") (pin "2") (pinfunction "2_2") (pintype "passive"))
      (node (ref "R75") (pin "2") (pinfunction "2_2") (pintype "passive"))
      (node (ref "R76") (pin "2") (pinfunction "2_2") (pintype "passive"))
      (node (ref "R77") (pin "2") (pinfunction "2_2") (pintype "passive"))
      (node (ref "R78") (pin "2") (pinfunction "2_2") (pintype "passive"))
      (node (ref "R79") (pin "2") (pinfunction "2_2") (pintype "passive"))
      (node (ref "R8") (pin "2") (pinfunction "2_2") (pintype "passive"))
      (node (ref "R80") (pin "2") (pinfunction "2_2") (pintype "passive"))
      (node (ref "R9") (pin "2") (pinfunction "2_2") (pintype "passive"))
    )
    (net (code "79") (name "unconnected-(JP1-Pad15)") (class "Default")
      (node (ref "JP1") (pin "15") (pinfunction "15_15") (pintype "passive"))
    )
    (net (code "80") (name "unconnected-(JP1-Pad16)") (class "Default")
      (node (ref "JP1") (pin "16") (pinfunction "16_16") (pintype "passive"))
    )
    (net (code "81") (name "unconnected-(JP1-Pad17)") (class "Default")
      (node (ref "JP1") (pin "17") (pinfunction "17_17") (pintype "passive"))
    )
    (net (code "82") (name "unconnected-(JP1-Pad18)") (class "Default")
      (node (ref "JP1") (pin "18") (pinfunction "18_18") (pintype "passive"))
    )
    (net (code "83") (name "unconnected-(JP1-Pad19)") (class "Default")
      (node (ref "JP1") (pin "19") (pinfunction "19_19") (pintype "passive"))
    )
    (net (code "84") (name "unconnected-(JP1-Pad20)") (class "Default")
      (node (ref "JP1") (pin "20") (pinfunction "20_20") (pintype "passive"))
    )
    (net (code "85") (name "unconnected-(JP1-Pad21)") (class "Default")
      (node (ref "JP1") (pin "21") (pinfunction "21_21") (pintype "passive"))
    )
    (net (code "86") (name "unconnected-(JP1-Pad22)") (class "Default")
      (node (ref "JP1") (pin "22") (pinfunction "22_22") (pintype "passive"))
    )
    (net (code "87") (name "unconnected-(JP1-Pad23)") (class "Default")
      (node (ref "JP1") (pin "23") (pinfunction "23_23") (pintype "passive"))
    )
    (net (code "88") (name "unconnected-(JP1-Pad24)") (class "Default")
      (node (ref "JP1") (pin "24") (pinfunction "24_24") (pintype "passive"))
    )
    (net (code "89") (name "unconnected-(JP1-Pad25)") (class "Default")
      (node (ref "JP1") (pin "25") (pinfunction "25_25") (pintype "passive"))
    )
    (net (code "90") (name "unconnected-(JP1-Pad26)") (class "Default")
      (node (ref "JP1") (pin "26") (pinfunction "26_26") (pintype "passive"))
    )
    (net (code "91") (name "unconnected-(JP1-Pad27)") (class "Default")
      (node (ref "JP1") (pin "27") (pinfunction "27_27") (pintype "passive"))
    )
    (net (code "92") (name "unconnected-(JP1-Pad28)") (class "Default")
      (node (ref "JP1") (pin "28") (pinfunction "28_28") (pintype "passive"))
    )
    (net (code "93") (name "{slash}CLK") (class "Default")
      (node (ref "Q102") (pin "1") (pinfunction "G_1") (pintype "bidirectional"))
      (node (ref "Q11") (pin "1") (pinfunction "G_1") (pintype "bidirectional"))
      (node (ref "Q14") (pin "1") (pinfunction "G_1") (pintype "bidirectional"))
      (node (ref "Q153") (pin "1") (pinfunction "G_1") (pintype "bidirectional"))
      (node (ref "Q156") (pin "1") (pinfunction "G_1") (pintype "bidirectional"))
      (node (ref "Q171") (pin "1") (pinfunction "G_1") (pintype "bidirectional"))
      (node (ref "Q174") (pin "1") (pinfunction "G_1") (pintype "bidirectional"))
      (node (ref "Q29") (pin "1") (pinfunction "G_1") (pintype "bidirectional"))
      (node (ref "Q32") (pin "1") (pinfunction "G_1") (pintype "bidirectional"))
      (node (ref "Q81") (pin "1") (pinfunction "G_1") (pintype "bidirectional"))
      (node (ref "Q84") (pin "1") (pinfunction "G_1") (pintype "bidirectional"))
      (node (ref "Q99") (pin "1") (pinfunction "G_1") (pintype "bidirectional"))
      (node (ref "SJ14") (pin "2") (pinfunction "2_2") (pintype "passive"))
    )
    (net (code "94") (name "{slash}Q0") (class "Default")
      (node (ref "Q115") (pin "1") (pinfunction "G_1") (pintype "bidirectional"))
      (node (ref "Q13") (pin "1") (pinfunction "G_1") (pintype "bidirectional"))
      (node (ref "Q16") (pin "3") (pinfunction "D_3") (pintype "bidirectional"))
      (node (ref "Q17") (pin "3") (pinfunction "D_3") (pintype "bidirectional"))
      (node (ref "Q25") (pin "1") (pinfunction "G_1") (pintype "bidirectional"))
      (node (ref "Q46") (pin "1") (pinfunction "G_1") (pintype "bidirectional"))
      (node (ref "R8") (pin "1") (pinfunction "1_1") (pintype "passive"))
    )
    (net (code "95") (name "{slash}Q1") (class "Default")
      (node (ref "Q122") (pin "1") (pinfunction "G_1") (pintype "bidirectional"))
      (node (ref "Q31") (pin "1") (pinfunction "G_1") (pintype "bidirectional"))
      (node (ref "Q34") (pin "3") (pinfunction "D_3") (pintype "bidirectional"))
      (node (ref "Q35") (pin "3") (pinfunction "D_3") (pintype "bidirectional"))
      (node (ref "Q55") (pin "1") (pinfunction "G_1") (pintype "bidirectional"))
      (node (ref "Q77") (pin "1") (pinfunction "G_1") (pintype "bidirectional"))
      (node (ref "R16") (pin "1") (pinfunction "1_1") (pintype "passive"))
    )
    (net (code "96") (name "{slash}Q2") (class "Default")
      (node (ref "Q128") (pin "1") (pinfunction "G_1") (pintype "bidirectional"))
      (node (ref "Q61") (pin "1") (pinfunction "G_1") (pintype "bidirectional"))
      (node (ref "Q83") (pin "1") (pinfunction "G_1") (pintype "bidirectional"))
      (node (ref "Q86") (pin "3") (pinfunction "D_3") (pintype "bidirectional"))
      (node (ref "Q87") (pin "3") (pinfunction "D_3") (pintype "bidirectional"))
      (node (ref "Q95") (pin "1") (pinfunction "G_1") (pintype "bidirectional"))
      (node (ref "R40") (pin "1") (pinfunction "1_1") (pintype "passive"))
    )
    (net (code "97") (name "{slash}Q3") (class "Default")
      (node (ref "Q101") (pin "1") (pinfunction "G_1") (pintype "bidirectional"))
      (node (ref "Q104") (pin "3") (pinfunction "D_3") (pintype "bidirectional"))
      (node (ref "Q105") (pin "3") (pinfunction "D_3") (pintype "bidirectional"))
      (node (ref "Q134") (pin "1") (pinfunction "G_1") (pintype "bidirectional"))
      (node (ref "Q149") (pin "1") (pinfunction "G_1") (pintype "bidirectional"))
      (node (ref "Q67") (pin "1") (pinfunction "G_1") (pintype "bidirectional"))
      (node (ref "R48") (pin "1") (pinfunction "1_1") (pintype "passive"))
    )
    (net (code "98") (name "{slash}Q4") (class "Default")
      (node (ref "Q109") (pin "1") (pinfunction "G_1") (pintype "bidirectional"))
      (node (ref "Q140") (pin "1") (pinfunction "G_1") (pintype "bidirectional"))
      (node (ref "Q155") (pin "1") (pinfunction "G_1") (pintype "bidirectional"))
      (node (ref "Q158") (pin "3") (pinfunction "D_3") (pintype "bidirectional"))
      (node (ref "Q159") (pin "3") (pinfunction "D_3") (pintype "bidirectional"))
      (node (ref "Q167") (pin "1") (pinfunction "G_1") (pintype "bidirectional"))
      (node (ref "R72") (pin "1") (pinfunction "1_1") (pintype "passive"))
    )
    (net (code "99") (name "{slash}Q5") (class "Default")
      (node (ref "Q116") (pin "1") (pinfunction "G_1") (pintype "bidirectional"))
      (node (ref "Q173") (pin "1") (pinfunction "G_1") (pintype "bidirectional"))
      (node (ref "Q176") (pin "3") (pinfunction "D_3") (pintype "bidirectional"))
      (node (ref "Q177") (pin "3") (pinfunction "D_3") (pintype "bidirectional"))
      (node (ref "Q182") (pin "1") (pinfunction "G_1") (pintype "bidirectional"))
      (node (ref "Q4") (pin "1") (pinfunction "G_1") (pintype "bidirectional"))
      (node (ref "R80") (pin "1") (pinfunction "1_1") (pintype "passive"))
    )
  )
)
